# WAB_1x4_HSMC_slots.net
KiCad netlist of a schematic drawn in Altium Designer
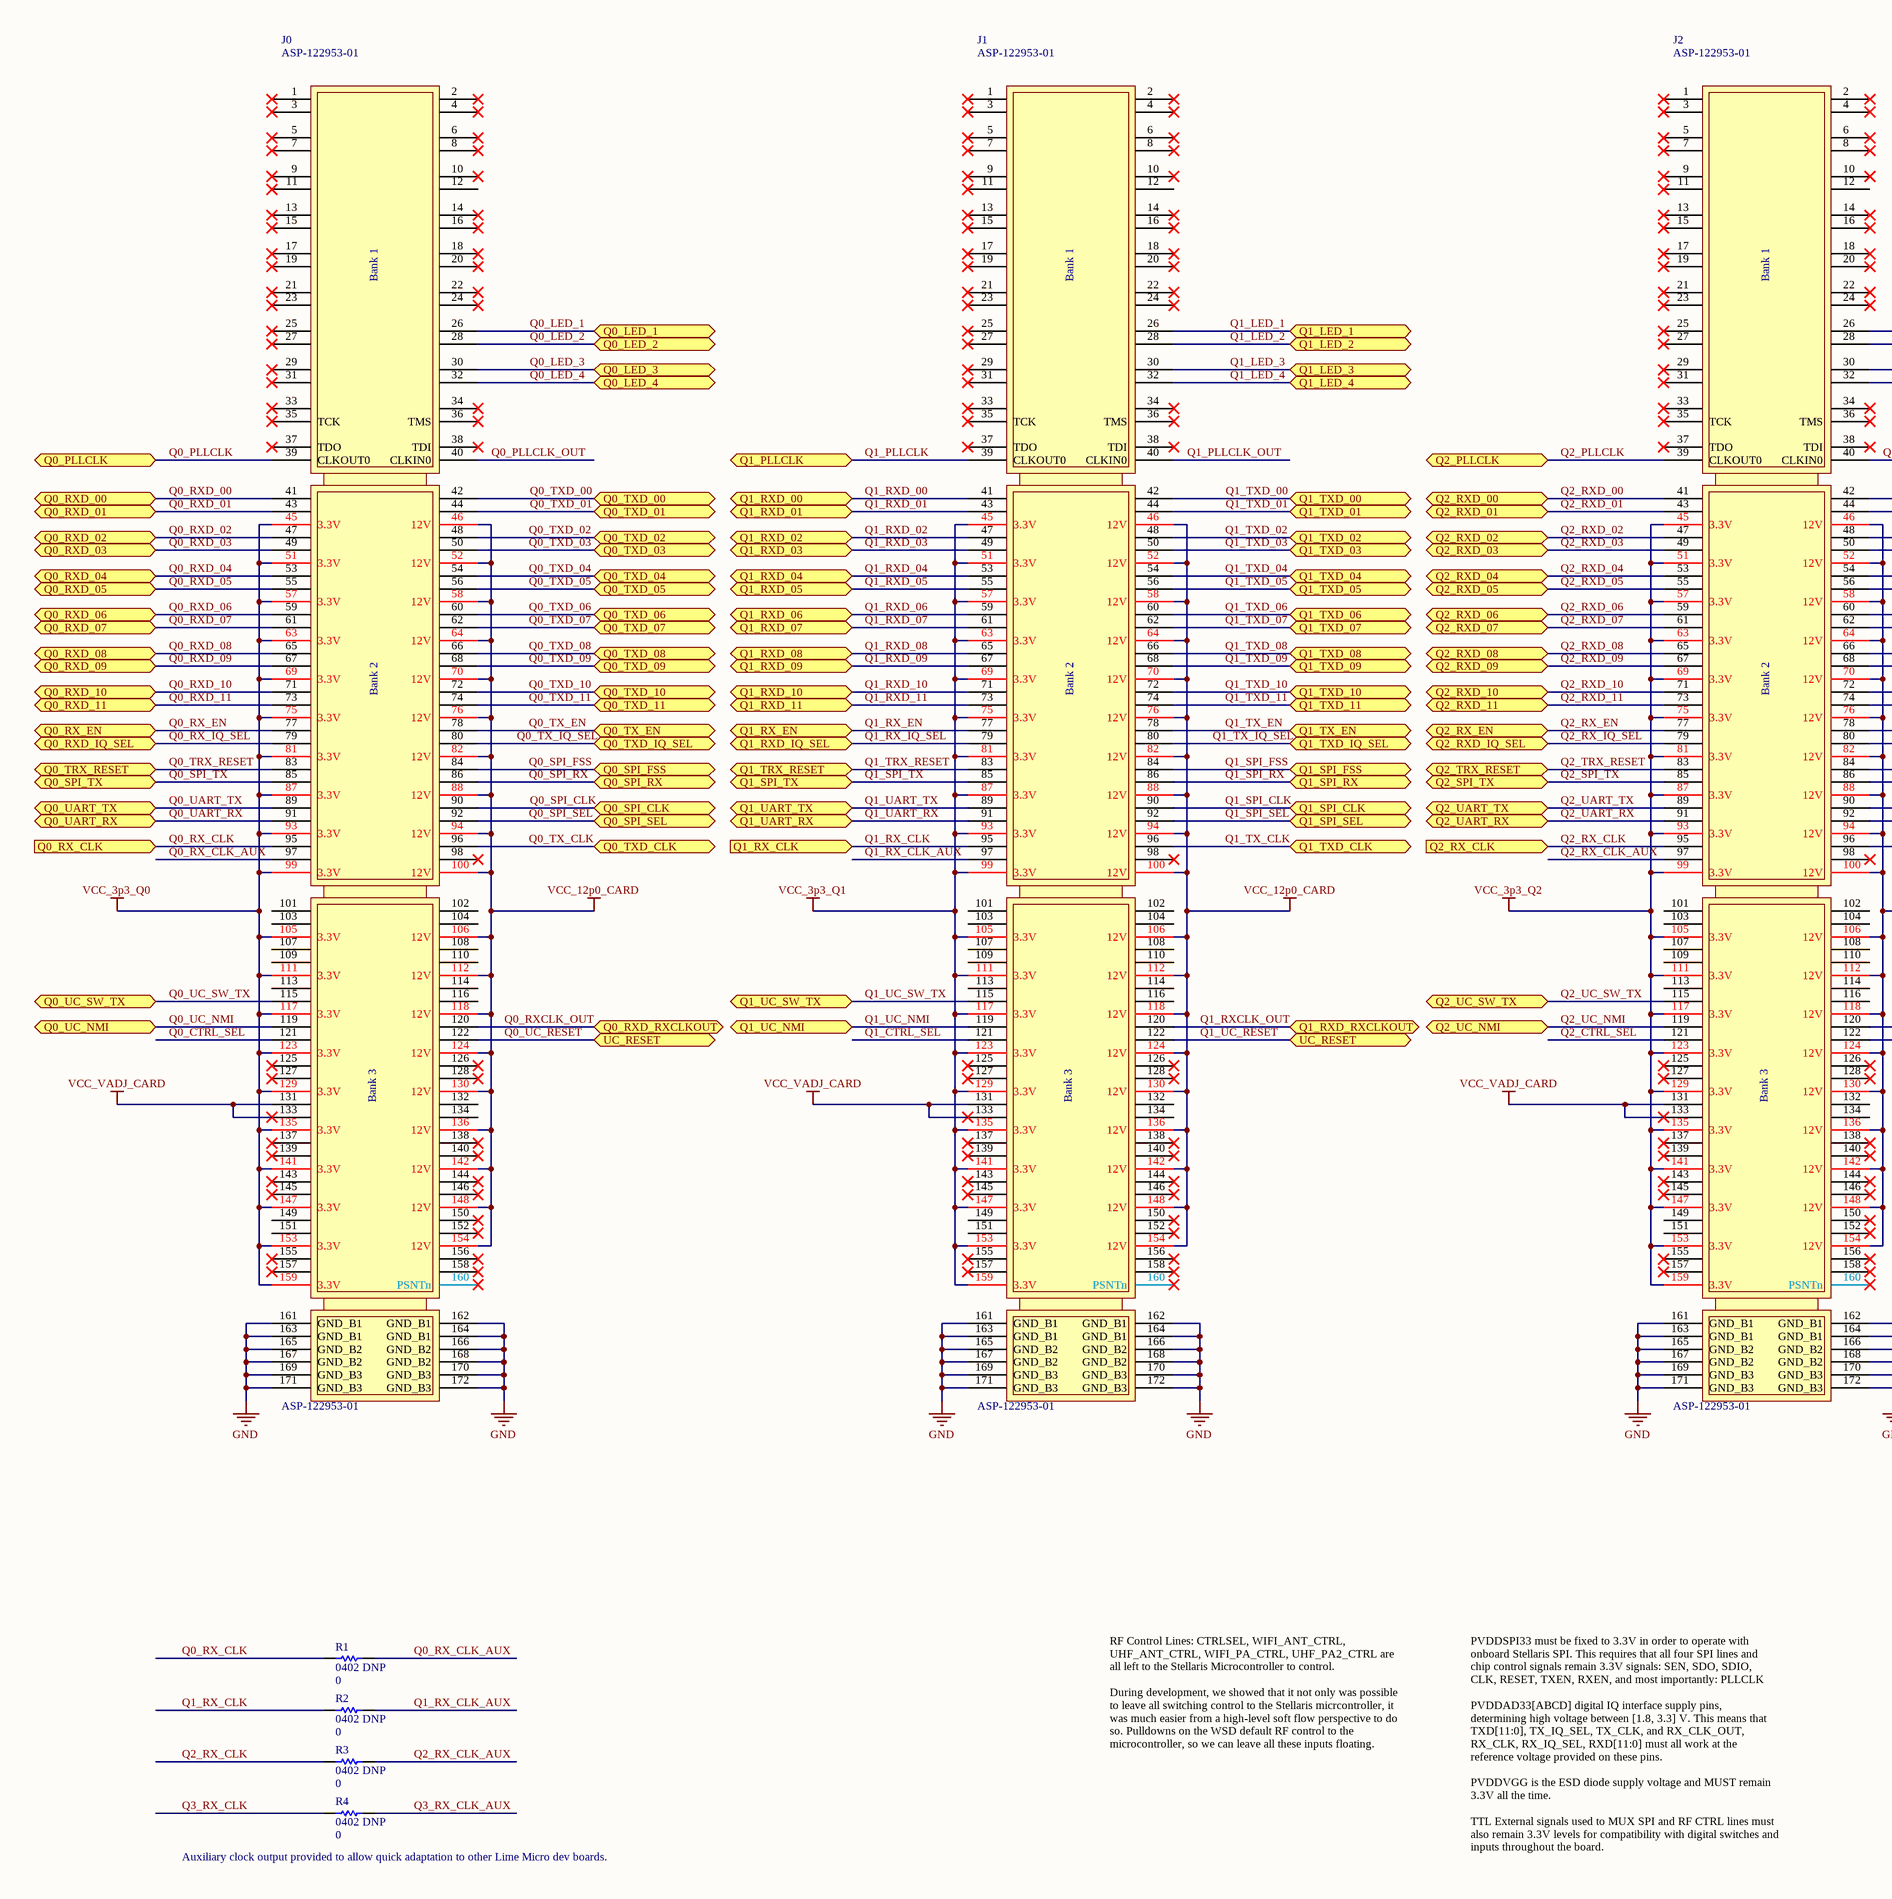
[diagram p0: WAB_1x4_HSMC_slots.SchDoc, left]
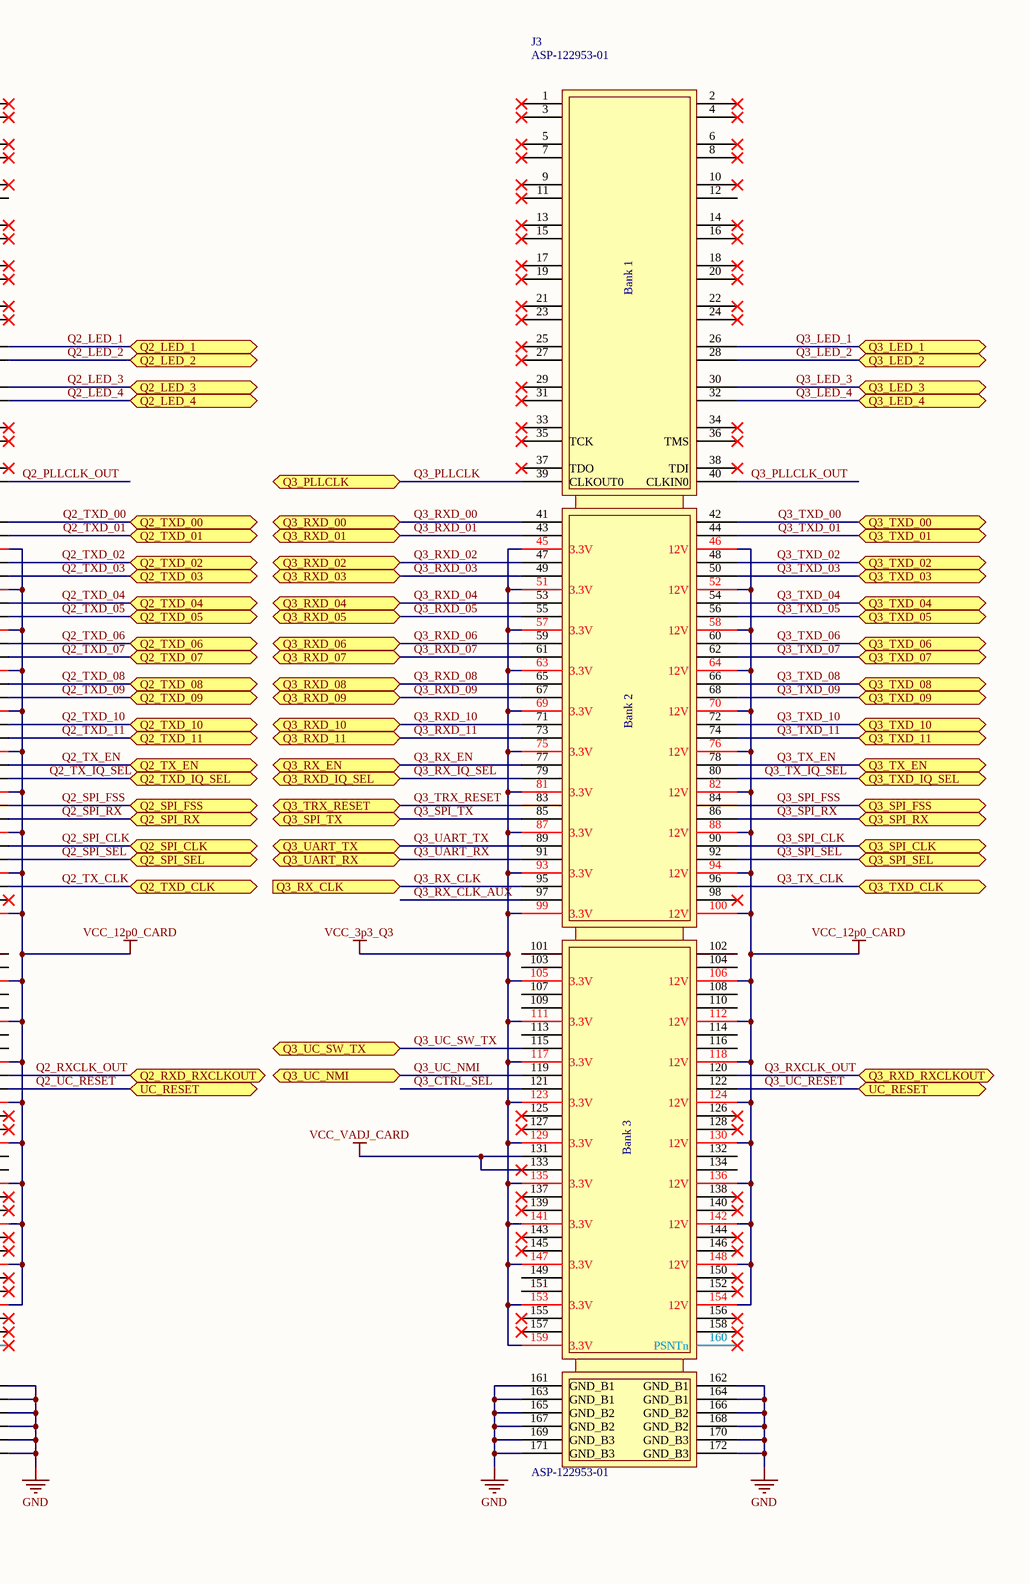
[diagram p1: WAB_1x4_HSMC_slots.SchDoc, right]

(export (version "E")
  (design (tool "Eeschema 10.0.6"))
  (components
    (comp (ref "J0")
      (value "ASP-122953-01")
      (footprint "ASP-122953-01_v3")
      (description "Samtec HSMC Host Connector (Female)")
      (libsource (lib "RNG_Parts") (part "ASP-122953-01"))
    )
    (comp (ref "J1")
      (value "ASP-122953-01")
      (footprint "ASP-122953-01_v3")
      (description "Samtec HSMC Host Connector (Female)")
      (libsource (lib "RNG_Parts") (part "ASP-122953-01"))
    )
    (comp (ref "J2")
      (value "ASP-122953-01")
      (footprint "ASP-122953-01_v3")
      (description "Samtec HSMC Host Connector (Female)")
      (libsource (lib "RNG_Parts") (part "ASP-122953-01"))
    )
    (comp (ref "J3")
      (value "ASP-122953-01")
      (footprint "ASP-122953-01_v3")
      (description "Samtec HSMC Host Connector (Female)")
      (libsource (lib "RNG_Parts") (part "ASP-122953-01"))
    )
    (comp (ref "R1")
      (value "0402 DNP")
      (footprint "0402_SMT_RES")
      (description "0402 SMT Resistor")
      (fields (field (name "ALTIUM_VALUE") "0"))
      (libsource (lib "RNG_Parts") (part "Res_0402"))
    )
    (comp (ref "R2")
      (value "0402 DNP")
      (footprint "0402_SMT_RES")
      (description "0402 SMT Resistor")
      (fields (field (name "ALTIUM_VALUE") "0"))
      (libsource (lib "RNG_Parts") (part "Res_0402"))
    )
    (comp (ref "R3")
      (value "0402 DNP")
      (footprint "0402_SMT_RES")
      (description "0402 SMT Resistor")
      (fields (field (name "ALTIUM_VALUE") "0"))
      (libsource (lib "RNG_Parts") (part "Res_0402"))
    )
    (comp (ref "R4")
      (value "0402 DNP")
      (footprint "0402_SMT_RES")
      (description "0402 SMT Resistor")
      (fields (field (name "ALTIUM_VALUE") "0"))
      (libsource (lib "RNG_Parts") (part "Res_0402"))
    )
  )
  (nets
    (net (code "1") (name "/Q0_CTRL_SEL") (class "Default")
      (node (ref "J0") (pin "121") (pinfunction "121_121") (pintype "passive"))
    )
    (net (code "2") (name "/Q0_LED_1") (class "Default")
      (node (ref "J0") (pin "26") (pinfunction "26_26") (pintype "passive"))
    )
    (net (code "3") (name "/Q0_LED_2") (class "Default")
      (node (ref "J0") (pin "28") (pinfunction "28_28") (pintype "passive"))
    )
    (net (code "4") (name "/Q0_LED_3") (class "Default")
      (node (ref "J0") (pin "30") (pinfunction "30_30") (pintype "passive"))
    )
    (net (code "5") (name "/Q0_LED_4") (class "Default")
      (node (ref "J0") (pin "32") (pinfunction "32_32") (pintype "passive"))
    )
    (net (code "6") (name "/Q0_PLLCLK") (class "Default")
      (node (ref "J0") (pin "39") (pinfunction "CLKOUT0_39") (pintype "passive"))
    )
    (net (code "7") (name "/Q0_PLLCLK_OUT") (class "Default")
      (node (ref "J0") (pin "40") (pinfunction "CLKIN0_40") (pintype "power_in"))
    )
    (net (code "8") (name "/Q0_RXCLK_OUT") (class "Default")
      (node (ref "J0") (pin "120") (pinfunction "120_120") (pintype "passive"))
    )
    (net (code "9") (name "/Q0_RXD_00") (class "Default")
      (node (ref "J0") (pin "41") (pinfunction "41_41") (pintype "passive"))
    )
    (net (code "10") (name "/Q0_RXD_01") (class "Default")
      (node (ref "J0") (pin "43") (pinfunction "43_43") (pintype "passive"))
    )
    (net (code "11") (name "/Q0_RXD_02") (class "Default")
      (node (ref "J0") (pin "47") (pinfunction "47_47") (pintype "passive"))
    )
    (net (code "12") (name "/Q0_RXD_03") (class "Default")
      (node (ref "J0") (pin "49") (pinfunction "49_49") (pintype "passive"))
    )
    (net (code "13") (name "/Q0_RXD_04") (class "Default")
      (node (ref "J0") (pin "53") (pinfunction "53_53") (pintype "passive"))
    )
    (net (code "14") (name "/Q0_RXD_05") (class "Default")
      (node (ref "J0") (pin "55") (pinfunction "55_55") (pintype "passive"))
    )
    (net (code "15") (name "/Q0_RXD_06") (class "Default")
      (node (ref "J0") (pin "59") (pinfunction "59_59") (pintype "passive"))
    )
    (net (code "16") (name "/Q0_RXD_07") (class "Default")
      (node (ref "J0") (pin "61") (pinfunction "61_61") (pintype "passive"))
    )
    (net (code "17") (name "/Q0_RXD_08") (class "Default")
      (node (ref "J0") (pin "65") (pinfunction "65_65") (pintype "passive"))
    )
    (net (code "18") (name "/Q0_RXD_09") (class "Default")
      (node (ref "J0") (pin "67") (pinfunction "67_67") (pintype "passive"))
    )
    (net (code "19") (name "/Q0_RXD_10") (class "Default")
      (node (ref "J0") (pin "71") (pinfunction "71_71") (pintype "passive"))
    )
    (net (code "20") (name "/Q0_RXD_11") (class "Default")
      (node (ref "J0") (pin "73") (pinfunction "73_73") (pintype "passive"))
    )
    (net (code "21") (name "/Q0_RX_CLK") (class "Default")
      (node (ref "J0") (pin "95") (pinfunction "95_95") (pintype "passive"))
      (node (ref "R1") (pin "1") (pinfunction "1_1") (pintype "passive"))
    )
    (net (code "22") (name "/Q0_RX_CLK_AUX") (class "Default")
      (node (ref "J0") (pin "97") (pinfunction "97_97") (pintype "passive"))
      (node (ref "R1") (pin "2") (pinfunction "2_2") (pintype "passive"))
    )
    (net (code "23") (name "/Q0_RX_EN") (class "Default")
      (node (ref "J0") (pin "77") (pinfunction "77_77") (pintype "passive"))
    )
    (net (code "24") (name "/Q0_RX_IQ_SEL") (class "Default")
      (node (ref "J0") (pin "79") (pinfunction "79_79") (pintype "passive"))
    )
    (net (code "25") (name "/Q0_SPI_CLK") (class "Default")
      (node (ref "J0") (pin "90") (pinfunction "90_90") (pintype "passive"))
    )
    (net (code "26") (name "/Q0_SPI_FSS") (class "Default")
      (node (ref "J0") (pin "84") (pinfunction "84_84") (pintype "passive"))
    )
    (net (code "27") (name "/Q0_SPI_RX") (class "Default")
      (node (ref "J0") (pin "86") (pinfunction "86_86") (pintype "passive"))
    )
    (net (code "28") (name "/Q0_SPI_SEL") (class "Default")
      (node (ref "J0") (pin "92") (pinfunction "92_92") (pintype "passive"))
    )
    (net (code "29") (name "/Q0_SPI_TX") (class "Default")
      (node (ref "J0") (pin "85") (pinfunction "85_85") (pintype "passive"))
    )
    (net (code "30") (name "/Q0_TRX_RESET") (class "Default")
      (node (ref "J0") (pin "83") (pinfunction "83_83") (pintype "passive"))
    )
    (net (code "31") (name "/Q0_TXD_00") (class "Default")
      (node (ref "J0") (pin "42") (pinfunction "42_42") (pintype "passive"))
    )
    (net (code "32") (name "/Q0_TXD_01") (class "Default")
      (node (ref "J0") (pin "44") (pinfunction "44_44") (pintype "passive"))
    )
    (net (code "33") (name "/Q0_TXD_02") (class "Default")
      (node (ref "J0") (pin "48") (pinfunction "48_48") (pintype "passive"))
    )
    (net (code "34") (name "/Q0_TXD_03") (class "Default")
      (node (ref "J0") (pin "50") (pinfunction "50_50") (pintype "passive"))
    )
    (net (code "35") (name "/Q0_TXD_04") (class "Default")
      (node (ref "J0") (pin "54") (pinfunction "54_54") (pintype "passive"))
    )
    (net (code "36") (name "/Q0_TXD_05") (class "Default")
      (node (ref "J0") (pin "56") (pinfunction "56_56") (pintype "passive"))
    )
    (net (code "37") (name "/Q0_TXD_06") (class "Default")
      (node (ref "J0") (pin "60") (pinfunction "60_60") (pintype "passive"))
    )
    (net (code "38") (name "/Q0_TXD_07") (class "Default")
      (node (ref "J0") (pin "62") (pinfunction "62_62") (pintype "passive"))
    )
    (net (code "39") (name "/Q0_TXD_08") (class "Default")
      (node (ref "J0") (pin "66") (pinfunction "66_66") (pintype "passive"))
    )
    (net (code "40") (name "/Q0_TXD_09") (class "Default")
      (node (ref "J0") (pin "68") (pinfunction "68_68") (pintype "passive"))
    )
    (net (code "41") (name "/Q0_TXD_10") (class "Default")
      (node (ref "J0") (pin "72") (pinfunction "72_72") (pintype "passive"))
    )
    (net (code "42") (name "/Q0_TXD_11") (class "Default")
      (node (ref "J0") (pin "74") (pinfunction "74_74") (pintype "passive"))
    )
    (net (code "43") (name "/Q0_TX_CLK") (class "Default")
      (node (ref "J0") (pin "96") (pinfunction "96_96") (pintype "passive"))
    )
    (net (code "44") (name "/Q0_TX_EN") (class "Default")
      (node (ref "J0") (pin "78") (pinfunction "78_78") (pintype "passive"))
    )
    (net (code "45") (name "/Q0_TX_IQ_SEL") (class "Default")
      (node (ref "J0") (pin "80") (pinfunction "80_80") (pintype "passive"))
    )
    (net (code "46") (name "/Q0_UART_RX") (class "Default")
      (node (ref "J0") (pin "91") (pinfunction "91_91") (pintype "passive"))
    )
    (net (code "47") (name "/Q0_UART_TX") (class "Default")
      (node (ref "J0") (pin "89") (pinfunction "89_89") (pintype "passive"))
    )
    (net (code "48") (name "/Q0_UC_NMI") (class "Default")
      (node (ref "J0") (pin "119") (pinfunction "119_119") (pintype "passive"))
    )
    (net (code "49") (name "/Q0_UC_RESET") (class "Default")
      (node (ref "J0") (pin "122") (pinfunction "122_122") (pintype "passive"))
      (node (ref "J1") (pin "122") (pinfunction "122_122") (pintype "passive"))
      (node (ref "J2") (pin "122") (pinfunction "122_122") (pintype "passive"))
      (node (ref "J3") (pin "122") (pinfunction "122_122") (pintype "passive"))
    )
    (net (code "50") (name "/Q0_UC_SW_TX") (class "Default")
      (node (ref "J0") (pin "115") (pinfunction "115_115") (pintype "passive"))
    )
    (net (code "51") (name "/Q1_CTRL_SEL") (class "Default")
      (node (ref "J1") (pin "121") (pinfunction "121_121") (pintype "passive"))
    )
    (net (code "52") (name "/Q1_LED_1") (class "Default")
      (node (ref "J1") (pin "26") (pinfunction "26_26") (pintype "passive"))
    )
    (net (code "53") (name "/Q1_LED_2") (class "Default")
      (node (ref "J1") (pin "28") (pinfunction "28_28") (pintype "passive"))
    )
    (net (code "54") (name "/Q1_LED_3") (class "Default")
      (node (ref "J1") (pin "30") (pinfunction "30_30") (pintype "passive"))
    )
    (net (code "55") (name "/Q1_LED_4") (class "Default")
      (node (ref "J1") (pin "32") (pinfunction "32_32") (pintype "passive"))
    )
    (net (code "56") (name "/Q1_PLLCLK") (class "Default")
      (node (ref "J1") (pin "39") (pinfunction "CLKOUT0_39") (pintype "passive"))
    )
    (net (code "57") (name "/Q1_PLLCLK_OUT") (class "Default")
      (node (ref "J1") (pin "40") (pinfunction "CLKIN0_40") (pintype "power_in"))
    )
    (net (code "58") (name "/Q1_RXCLK_OUT") (class "Default")
      (node (ref "J1") (pin "120") (pinfunction "120_120") (pintype "passive"))
    )
    (net (code "59") (name "/Q1_RXD_00") (class "Default")
      (node (ref "J1") (pin "41") (pinfunction "41_41") (pintype "passive"))
    )
    (net (code "60") (name "/Q1_RXD_01") (class "Default")
      (node (ref "J1") (pin "43") (pinfunction "43_43") (pintype "passive"))
    )
    (net (code "61") (name "/Q1_RXD_02") (class "Default")
      (node (ref "J1") (pin "47") (pinfunction "47_47") (pintype "passive"))
    )
    (net (code "62") (name "/Q1_RXD_03") (class "Default")
      (node (ref "J1") (pin "49") (pinfunction "49_49") (pintype "passive"))
    )
    (net (code "63") (name "/Q1_RXD_04") (class "Default")
      (node (ref "J1") (pin "53") (pinfunction "53_53") (pintype "passive"))
    )
    (net (code "64") (name "/Q1_RXD_05") (class "Default")
      (node (ref "J1") (pin "55") (pinfunction "55_55") (pintype "passive"))
    )
    (net (code "65") (name "/Q1_RXD_06") (class "Default")
      (node (ref "J1") (pin "59") (pinfunction "59_59") (pintype "passive"))
    )
    (net (code "66") (name "/Q1_RXD_07") (class "Default")
      (node (ref "J1") (pin "61") (pinfunction "61_61") (pintype "passive"))
    )
    (net (code "67") (name "/Q1_RXD_08") (class "Default")
      (node (ref "J1") (pin "65") (pinfunction "65_65") (pintype "passive"))
    )
    (net (code "68") (name "/Q1_RXD_09") (class "Default")
      (node (ref "J1") (pin "67") (pinfunction "67_67") (pintype "passive"))
    )
    (net (code "69") (name "/Q1_RXD_10") (class "Default")
      (node (ref "J1") (pin "71") (pinfunction "71_71") (pintype "passive"))
    )
    (net (code "70") (name "/Q1_RXD_11") (class "Default")
      (node (ref "J1") (pin "73") (pinfunction "73_73") (pintype "passive"))
    )
    (net (code "71") (name "/Q1_RX_CLK") (class "Default")
      (node (ref "J1") (pin "95") (pinfunction "95_95") (pintype "passive"))
      (node (ref "R2") (pin "1") (pinfunction "1_1") (pintype "passive"))
    )
    (net (code "72") (name "/Q1_RX_CLK_AUX") (class "Default")
      (node (ref "J1") (pin "97") (pinfunction "97_97") (pintype "passive"))
      (node (ref "R2") (pin "2") (pinfunction "2_2") (pintype "passive"))
    )
    (net (code "73") (name "/Q1_RX_EN") (class "Default")
      (node (ref "J1") (pin "77") (pinfunction "77_77") (pintype "passive"))
    )
    (net (code "74") (name "/Q1_RX_IQ_SEL") (class "Default")
      (node (ref "J1") (pin "79") (pinfunction "79_79") (pintype "passive"))
    )
    (net (code "75") (name "/Q1_SPI_CLK") (class "Default")
      (node (ref "J1") (pin "90") (pinfunction "90_90") (pintype "passive"))
    )
    (net (code "76") (name "/Q1_SPI_FSS") (class "Default")
      (node (ref "J1") (pin "84") (pinfunction "84_84") (pintype "passive"))
    )
    (net (code "77") (name "/Q1_SPI_RX") (class "Default")
      (node (ref "J1") (pin "86") (pinfunction "86_86") (pintype "passive"))
    )
    (net (code "78") (name "/Q1_SPI_SEL") (class "Default")
      (node (ref "J1") (pin "92") (pinfunction "92_92") (pintype "passive"))
    )
    (net (code "79") (name "/Q1_SPI_TX") (class "Default")
      (node (ref "J1") (pin "85") (pinfunction "85_85") (pintype "passive"))
    )
    (net (code "80") (name "/Q1_TRX_RESET") (class "Default")
      (node (ref "J1") (pin "83") (pinfunction "83_83") (pintype "passive"))
    )
    (net (code "81") (name "/Q1_TXD_00") (class "Default")
      (node (ref "J1") (pin "42") (pinfunction "42_42") (pintype "passive"))
    )
    (net (code "82") (name "/Q1_TXD_01") (class "Default")
      (node (ref "J1") (pin "44") (pinfunction "44_44") (pintype "passive"))
    )
    (net (code "83") (name "/Q1_TXD_02") (class "Default")
      (node (ref "J1") (pin "48") (pinfunction "48_48") (pintype "passive"))
    )
    (net (code "84") (name "/Q1_TXD_03") (class "Default")
      (node (ref "J1") (pin "50") (pinfunction "50_50") (pintype "passive"))
    )
    (net (code "85") (name "/Q1_TXD_04") (class "Default")
      (node (ref "J1") (pin "54") (pinfunction "54_54") (pintype "passive"))
    )
    (net (code "86") (name "/Q1_TXD_05") (class "Default")
      (node (ref "J1") (pin "56") (pinfunction "56_56") (pintype "passive"))
    )
    (net (code "87") (name "/Q1_TXD_06") (class "Default")
      (node (ref "J1") (pin "60") (pinfunction "60_60") (pintype "passive"))
    )
    (net (code "88") (name "/Q1_TXD_07") (class "Default")
      (node (ref "J1") (pin "62") (pinfunction "62_62") (pintype "passive"))
    )
    (net (code "89") (name "/Q1_TXD_08") (class "Default")
      (node (ref "J1") (pin "66") (pinfunction "66_66") (pintype "passive"))
    )
    (net (code "90") (name "/Q1_TXD_09") (class "Default")
      (node (ref "J1") (pin "68") (pinfunction "68_68") (pintype "passive"))
    )
    (net (code "91") (name "/Q1_TXD_10") (class "Default")
      (node (ref "J1") (pin "72") (pinfunction "72_72") (pintype "passive"))
    )
    (net (code "92") (name "/Q1_TXD_11") (class "Default")
      (node (ref "J1") (pin "74") (pinfunction "74_74") (pintype "passive"))
    )
    (net (code "93") (name "/Q1_TX_CLK") (class "Default")
      (node (ref "J1") (pin "96") (pinfunction "96_96") (pintype "passive"))
    )
    (net (code "94") (name "/Q1_TX_EN") (class "Default")
      (node (ref "J1") (pin "78") (pinfunction "78_78") (pintype "passive"))
    )
    (net (code "95") (name "/Q1_TX_IQ_SEL") (class "Default")
      (node (ref "J1") (pin "80") (pinfunction "80_80") (pintype "passive"))
    )
    (net (code "96") (name "/Q1_UART_RX") (class "Default")
      (node (ref "J1") (pin "91") (pinfunction "91_91") (pintype "passive"))
    )
    (net (code "97") (name "/Q1_UART_TX") (class "Default")
      (node (ref "J1") (pin "89") (pinfunction "89_89") (pintype "passive"))
    )
    (net (code "98") (name "/Q1_UC_NMI") (class "Default")
      (node (ref "J1") (pin "119") (pinfunction "119_119") (pintype "passive"))
    )
    (net (code "99") (name "/Q1_UC_SW_TX") (class "Default")
      (node (ref "J1") (pin "115") (pinfunction "115_115") (pintype "passive"))
    )
    (net (code "100") (name "/Q2_CTRL_SEL") (class "Default")
      (node (ref "J2") (pin "121") (pinfunction "121_121") (pintype "passive"))
    )
    (net (code "101") (name "/Q2_LED_1") (class "Default")
      (node (ref "J2") (pin "26") (pinfunction "26_26") (pintype "passive"))
    )
    (net (code "102") (name "/Q2_LED_2") (class "Default")
      (node (ref "J2") (pin "28") (pinfunction "28_28") (pintype "passive"))
    )
    (net (code "103") (name "/Q2_LED_3") (class "Default")
      (node (ref "J2") (pin "30") (pinfunction "30_30") (pintype "passive"))
    )
    (net (code "104") (name "/Q2_LED_4") (class "Default")
      (node (ref "J2") (pin "32") (pinfunction "32_32") (pintype "passive"))
    )
    (net (code "105") (name "/Q2_PLLCLK") (class "Default")
      (node (ref "J2") (pin "39") (pinfunction "CLKOUT0_39") (pintype "passive"))
    )
    (net (code "106") (name "/Q2_PLLCLK_OUT") (class "Default")
      (node (ref "J2") (pin "40") (pinfunction "CLKIN0_40") (pintype "power_in"))
    )
    (net (code "107") (name "/Q2_RXCLK_OUT") (class "Default")
      (node (ref "J2") (pin "120") (pinfunction "120_120") (pintype "passive"))
    )
    (net (code "108") (name "/Q2_RXD_00") (class "Default")
      (node (ref "J2") (pin "41") (pinfunction "41_41") (pintype "passive"))
    )
    (net (code "109") (name "/Q2_RXD_01") (class "Default")
      (node (ref "J2") (pin "43") (pinfunction "43_43") (pintype "passive"))
    )
    (net (code "110") (name "/Q2_RXD_02") (class "Default")
      (node (ref "J2") (pin "47") (pinfunction "47_47") (pintype "passive"))
    )
    (net (code "111") (name "/Q2_RXD_03") (class "Default")
      (node (ref "J2") (pin "49") (pinfunction "49_49") (pintype "passive"))
    )
    (net (code "112") (name "/Q2_RXD_04") (class "Default")
      (node (ref "J2") (pin "53") (pinfunction "53_53") (pintype "passive"))
    )
    (net (code "113") (name "/Q2_RXD_05") (class "Default")
      (node (ref "J2") (pin "55") (pinfunction "55_55") (pintype "passive"))
    )
    (net (code "114") (name "/Q2_RXD_06") (class "Default")
      (node (ref "J2") (pin "59") (pinfunction "59_59") (pintype "passive"))
    )
    (net (code "115") (name "/Q2_RXD_07") (class "Default")
      (node (ref "J2") (pin "61") (pinfunction "61_61") (pintype "passive"))
    )
    (net (code "116") (name "/Q2_RXD_08") (class "Default")
      (node (ref "J2") (pin "65") (pinfunction "65_65") (pintype "passive"))
    )
    (net (code "117") (name "/Q2_RXD_09") (class "Default")
      (node (ref "J2") (pin "67") (pinfunction "67_67") (pintype "passive"))
    )
    (net (code "118") (name "/Q2_RXD_10") (class "Default")
      (node (ref "J2") (pin "71") (pinfunction "71_71") (pintype "passive"))
    )
    (net (code "119") (name "/Q2_RXD_11") (class "Default")
      (node (ref "J2") (pin "73") (pinfunction "73_73") (pintype "passive"))
    )
    (net (code "120") (name "/Q2_RX_CLK") (class "Default")
      (node (ref "J2") (pin "95") (pinfunction "95_95") (pintype "passive"))
      (node (ref "R3") (pin "1") (pinfunction "1_1") (pintype "passive"))
    )
    (net (code "121") (name "/Q2_RX_CLK_AUX") (class "Default")
      (node (ref "J2") (pin "97") (pinfunction "97_97") (pintype "passive"))
      (node (ref "R3") (pin "2") (pinfunction "2_2") (pintype "passive"))
    )
    (net (code "122") (name "/Q2_RX_EN") (class "Default")
      (node (ref "J2") (pin "77") (pinfunction "77_77") (pintype "passive"))
    )
    (net (code "123") (name "/Q2_RX_IQ_SEL") (class "Default")
      (node (ref "J2") (pin "79") (pinfunction "79_79") (pintype "passive"))
    )
    (net (code "124") (name "/Q2_SPI_CLK") (class "Default")
      (node (ref "J2") (pin "90") (pinfunction "90_90") (pintype "passive"))
    )
    (net (code "125") (name "/Q2_SPI_FSS") (class "Default")
      (node (ref "J2") (pin "84") (pinfunction "84_84") (pintype "passive"))
    )
    (net (code "126") (name "/Q2_SPI_RX") (class "Default")
      (node (ref "J2") (pin "86") (pinfunction "86_86") (pintype "passive"))
    )
    (net (code "127") (name "/Q2_SPI_SEL") (class "Default")
      (node (ref "J2") (pin "92") (pinfunction "92_92") (pintype "passive"))
    )
    (net (code "128") (name "/Q2_SPI_TX") (class "Default")
      (node (ref "J2") (pin "85") (pinfunction "85_85") (pintype "passive"))
    )
    (net (code "129") (name "/Q2_TRX_RESET") (class "Default")
      (node (ref "J2") (pin "83") (pinfunction "83_83") (pintype "passive"))
    )
    (net (code "130") (name "/Q2_TXD_00") (class "Default")
      (node (ref "J2") (pin "42") (pinfunction "42_42") (pintype "passive"))
    )
    (net (code "131") (name "/Q2_TXD_01") (class "Default")
      (node (ref "J2") (pin "44") (pinfunction "44_44") (pintype "passive"))
    )
    (net (code "132") (name "/Q2_TXD_02") (class "Default")
      (node (ref "J2") (pin "48") (pinfunction "48_48") (pintype "passive"))
    )
    (net (code "133") (name "/Q2_TXD_03") (class "Default")
      (node (ref "J2") (pin "50") (pinfunction "50_50") (pintype "passive"))
    )
    (net (code "134") (name "/Q2_TXD_04") (class "Default")
      (node (ref "J2") (pin "54") (pinfunction "54_54") (pintype "passive"))
    )
    (net (code "135") (name "/Q2_TXD_05") (class "Default")
      (node (ref "J2") (pin "56") (pinfunction "56_56") (pintype "passive"))
    )
    (net (code "136") (name "/Q2_TXD_06") (class "Default")
      (node (ref "J2") (pin "60") (pinfunction "60_60") (pintype "passive"))
    )
    (net (code "137") (name "/Q2_TXD_07") (class "Default")
      (node (ref "J2") (pin "62") (pinfunction "62_62") (pintype "passive"))
    )
    (net (code "138") (name "/Q2_TXD_08") (class "Default")
      (node (ref "J2") (pin "66") (pinfunction "66_66") (pintype "passive"))
    )
    (net (code "139") (name "/Q2_TXD_09") (class "Default")
      (node (ref "J2") (pin "68") (pinfunction "68_68") (pintype "passive"))
    )
    (net (code "140") (name "/Q2_TXD_10") (class "Default")
      (node (ref "J2") (pin "72") (pinfunction "72_72") (pintype "passive"))
    )
    (net (code "141") (name "/Q2_TXD_11") (class "Default")
      (node (ref "J2") (pin "74") (pinfunction "74_74") (pintype "passive"))
    )
    (net (code "142") (name "/Q2_TX_CLK") (class "Default")
      (node (ref "J2") (pin "96") (pinfunction "96_96") (pintype "passive"))
    )
    (net (code "143") (name "/Q2_TX_EN") (class "Default")
      (node (ref "J2") (pin "78") (pinfunction "78_78") (pintype "passive"))
    )
    (net (code "144") (name "/Q2_TX_IQ_SEL") (class "Default")
      (node (ref "J2") (pin "80") (pinfunction "80_80") (pintype "passive"))
    )
    (net (code "145") (name "/Q2_UART_RX") (class "Default")
      (node (ref "J2") (pin "91") (pinfunction "91_91") (pintype "passive"))
    )
    (net (code "146") (name "/Q2_UART_TX") (class "Default")
      (node (ref "J2") (pin "89") (pinfunction "89_89") (pintype "passive"))
    )
    (net (code "147") (name "/Q2_UC_NMI") (class "Default")
      (node (ref "J2") (pin "119") (pinfunction "119_119") (pintype "passive"))
    )
    (net (code "148") (name "/Q2_UC_SW_TX") (class "Default")
      (node (ref "J2") (pin "115") (pinfunction "115_115") (pintype "passive"))
    )
    (net (code "149") (name "/Q3_CTRL_SEL") (class "Default")
      (node (ref "J3") (pin "121") (pinfunction "121_121") (pintype "passive"))
    )
    (net (code "150") (name "/Q3_LED_1") (class "Default")
      (node (ref "J3") (pin "26") (pinfunction "26_26") (pintype "passive"))
    )
    (net (code "151") (name "/Q3_LED_2") (class "Default")
      (node (ref "J3") (pin "28") (pinfunction "28_28") (pintype "passive"))
    )
    (net (code "152") (name "/Q3_LED_3") (class "Default")
      (node (ref "J3") (pin "30") (pinfunction "30_30") (pintype "passive"))
    )
    (net (code "153") (name "/Q3_LED_4") (class "Default")
      (node (ref "J3") (pin "32") (pinfunction "32_32") (pintype "passive"))
    )
    (net (code "154") (name "/Q3_PLLCLK") (class "Default")
      (node (ref "J3") (pin "39") (pinfunction "CLKOUT0_39") (pintype "passive"))
    )
    (net (code "155") (name "/Q3_PLLCLK_OUT") (class "Default")
      (node (ref "J3") (pin "40") (pinfunction "CLKIN0_40") (pintype "power_in"))
    )
    (net (code "156") (name "/Q3_RXCLK_OUT") (class "Default")
      (node (ref "J3") (pin "120") (pinfunction "120_120") (pintype "passive"))
    )
    (net (code "157") (name "/Q3_RXD_00") (class "Default")
      (node (ref "J3") (pin "41") (pinfunction "41_41") (pintype "passive"))
    )
    (net (code "158") (name "/Q3_RXD_01") (class "Default")
      (node (ref "J3") (pin "43") (pinfunction "43_43") (pintype "passive"))
    )
    (net (code "159") (name "/Q3_RXD_02") (class "Default")
      (node (ref "J3") (pin "47") (pinfunction "47_47") (pintype "passive"))
    )
    (net (code "160") (name "/Q3_RXD_03") (class "Default")
      (node (ref "J3") (pin "49") (pinfunction "49_49") (pintype "passive"))
    )
    (net (code "161") (name "/Q3_RXD_04") (class "Default")
      (node (ref "J3") (pin "53") (pinfunction "53_53") (pintype "passive"))
    )
    (net (code "162") (name "/Q3_RXD_05") (class "Default")
      (node (ref "J3") (pin "55") (pinfunction "55_55") (pintype "passive"))
    )
    (net (code "163") (name "/Q3_RXD_06") (class "Default")
      (node (ref "J3") (pin "59") (pinfunction "59_59") (pintype "passive"))
    )
    (net (code "164") (name "/Q3_RXD_07") (class "Default")
      (node (ref "J3") (pin "61") (pinfunction "61_61") (pintype "passive"))
    )
    (net (code "165") (name "/Q3_RXD_08") (class "Default")
      (node (ref "J3") (pin "65") (pinfunction "65_65") (pintype "passive"))
    )
    (net (code "166") (name "/Q3_RXD_09") (class "Default")
      (node (ref "J3") (pin "67") (pinfunction "67_67") (pintype "passive"))
    )
    (net (code "167") (name "/Q3_RXD_10") (class "Default")
      (node (ref "J3") (pin "71") (pinfunction "71_71") (pintype "passive"))
    )
    (net (code "168") (name "/Q3_RXD_11") (class "Default")
      (node (ref "J3") (pin "73") (pinfunction "73_73") (pintype "passive"))
    )
    (net (code "169") (name "/Q3_RX_CLK") (class "Default")
      (node (ref "J3") (pin "95") (pinfunction "95_95") (pintype "passive"))
      (node (ref "R4") (pin "1") (pinfunction "1_1") (pintype "passive"))
    )
    (net (code "170") (name "/Q3_RX_CLK_AUX") (class "Default")
      (node (ref "J3") (pin "97") (pinfunction "97_97") (pintype "passive"))
      (node (ref "R4") (pin "2") (pinfunction "2_2") (pintype "passive"))
    )
    (net (code "171") (name "/Q3_RX_EN") (class "Default")
      (node (ref "J3") (pin "77") (pinfunction "77_77") (pintype "passive"))
    )
    (net (code "172") (name "/Q3_RX_IQ_SEL") (class "Default")
      (node (ref "J3") (pin "79") (pinfunction "79_79") (pintype "passive"))
    )
    (net (code "173") (name "/Q3_SPI_CLK") (class "Default")
      (node (ref "J3") (pin "90") (pinfunction "90_90") (pintype "passive"))
    )
    (net (code "174") (name "/Q3_SPI_FSS") (class "Default")
      (node (ref "J3") (pin "84") (pinfunction "84_84") (pintype "passive"))
    )
    (net (code "175") (name "/Q3_SPI_RX") (class "Default")
      (node (ref "J3") (pin "86") (pinfunction "86_86") (pintype "passive"))
    )
    (net (code "176") (name "/Q3_SPI_SEL") (class "Default")
      (node (ref "J3") (pin "92") (pinfunction "92_92") (pintype "passive"))
    )
    (net (code "177") (name "/Q3_SPI_TX") (class "Default")
      (node (ref "J3") (pin "85") (pinfunction "85_85") (pintype "passive"))
    )
    (net (code "178") (name "/Q3_TRX_RESET") (class "Default")
      (node (ref "J3") (pin "83") (pinfunction "83_83") (pintype "passive"))
    )
    (net (code "179") (name "/Q3_TXD_00") (class "Default")
      (node (ref "J3") (pin "42") (pinfunction "42_42") (pintype "passive"))
    )
    (net (code "180") (name "/Q3_TXD_01") (class "Default")
      (node (ref "J3") (pin "44") (pinfunction "44_44") (pintype "passive"))
    )
    (net (code "181") (name "/Q3_TXD_02") (class "Default")
      (node (ref "J3") (pin "48") (pinfunction "48_48") (pintype "passive"))
    )
    (net (code "182") (name "/Q3_TXD_03") (class "Default")
      (node (ref "J3") (pin "50") (pinfunction "50_50") (pintype "passive"))
    )
    (net (code "183") (name "/Q3_TXD_04") (class "Default")
      (node (ref "J3") (pin "54") (pinfunction "54_54") (pintype "passive"))
    )
    (net (code "184") (name "/Q3_TXD_05") (class "Default")
      (node (ref "J3") (pin "56") (pinfunction "56_56") (pintype "passive"))
    )
    (net (code "185") (name "/Q3_TXD_06") (class "Default")
      (node (ref "J3") (pin "60") (pinfunction "60_60") (pintype "passive"))
    )
    (net (code "186") (name "/Q3_TXD_07") (class "Default")
      (node (ref "J3") (pin "62") (pinfunction "62_62") (pintype "passive"))
    )
    (net (code "187") (name "/Q3_TXD_08") (class "Default")
      (node (ref "J3") (pin "66") (pinfunction "66_66") (pintype "passive"))
    )
    (net (code "188") (name "/Q3_TXD_09") (class "Default")
      (node (ref "J3") (pin "68") (pinfunction "68_68") (pintype "passive"))
    )
    (net (code "189") (name "/Q3_TXD_10") (class "Default")
      (node (ref "J3") (pin "72") (pinfunction "72_72") (pintype "passive"))
    )
    (net (code "190") (name "/Q3_TXD_11") (class "Default")
      (node (ref "J3") (pin "74") (pinfunction "74_74") (pintype "passive"))
    )
    (net (code "191") (name "/Q3_TX_CLK") (class "Default")
      (node (ref "J3") (pin "96") (pinfunction "96_96") (pintype "passive"))
    )
    (net (code "192") (name "/Q3_TX_EN") (class "Default")
      (node (ref "J3") (pin "78") (pinfunction "78_78") (pintype "passive"))
    )
    (net (code "193") (name "/Q3_TX_IQ_SEL") (class "Default")
      (node (ref "J3") (pin "80") (pinfunction "80_80") (pintype "passive"))
    )
    (net (code "194") (name "/Q3_UART_RX") (class "Default")
      (node (ref "J3") (pin "91") (pinfunction "91_91") (pintype "passive"))
    )
    (net (code "195") (name "/Q3_UART_TX") (class "Default")
      (node (ref "J3") (pin "89") (pinfunction "89_89") (pintype "passive"))
    )
    (net (code "196") (name "/Q3_UC_NMI") (class "Default")
      (node (ref "J3") (pin "119") (pinfunction "119_119") (pintype "passive"))
    )
    (net (code "197") (name "/Q3_UC_SW_TX") (class "Default")
      (node (ref "J3") (pin "115") (pinfunction "115_115") (pintype "passive"))
    )
    (net (code "198") (name "GND") (class "Default")
      (node (ref "J0") (pin "161") (pinfunction "GND_B1_161") (pintype "power_in"))
      (node (ref "J0") (pin "162") (pinfunction "GND_B1_162") (pintype "power_in"))
      (node (ref "J0") (pin "163") (pinfunction "GND_B1_163") (pintype "power_in"))
      (node (ref "J0") (pin "164") (pinfunction "GND_B1_164") (pintype "power_in"))
      (node (ref "J0") (pin "165") (pinfunction "GND_B2_165") (pintype "power_in"))
      (node (ref "J0") (pin "166") (pinfunction "GND_B2_166") (pintype "power_in"))
      (node (ref "J0") (pin "167") (pinfunction "GND_B2_167") (pintype "power_in"))
      (node (ref "J0") (pin "168") (pinfunction "GND_B2_168") (pintype "power_in"))
      (node (ref "J0") (pin "169") (pinfunction "GND_B3_169") (pintype "power_in"))
      (node (ref "J0") (pin "170") (pinfunction "GND_B3_170") (pintype "power_in"))
      (node (ref "J0") (pin "171") (pinfunction "GND_B3_171") (pintype "power_in"))
      (node (ref "J0") (pin "172") (pinfunction "GND_B3_172") (pintype "power_in"))
      (node (ref "J1") (pin "161") (pinfunction "GND_B1_161") (pintype "power_in"))
      (node (ref "J1") (pin "162") (pinfunction "GND_B1_162") (pintype "power_in"))
      (node (ref "J1") (pin "163") (pinfunction "GND_B1_163") (pintype "power_in"))
      (node (ref "J1") (pin "164") (pinfunction "GND_B1_164") (pintype "power_in"))
      (node (ref "J1") (pin "165") (pinfunction "GND_B2_165") (pintype "power_in"))
      (node (ref "J1") (pin "166") (pinfunction "GND_B2_166") (pintype "power_in"))
      (node (ref "J1") (pin "167") (pinfunction "GND_B2_167") (pintype "power_in"))
      (node (ref "J1") (pin "168") (pinfunction "GND_B2_168") (pintype "power_in"))
      (node (ref "J1") (pin "169") (pinfunction "GND_B3_169") (pintype "power_in"))
      (node (ref "J1") (pin "170") (pinfunction "GND_B3_170") (pintype "power_in"))
      (node (ref "J1") (pin "171") (pinfunction "GND_B3_171") (pintype "power_in"))
      (node (ref "J1") (pin "172") (pinfunction "GND_B3_172") (pintype "power_in"))
      (node (ref "J2") (pin "161") (pinfunction "GND_B1_161") (pintype "power_in"))
      (node (ref "J2") (pin "162") (pinfunction "GND_B1_162") (pintype "power_in"))
      (node (ref "J2") (pin "163") (pinfunction "GND_B1_163") (pintype "power_in"))
      (node (ref "J2") (pin "164") (pinfunction "GND_B1_164") (pintype "power_in"))
      (node (ref "J2") (pin "165") (pinfunction "GND_B2_165") (pintype "power_in"))
      (node (ref "J2") (pin "166") (pinfunction "GND_B2_166") (pintype "power_in"))
      (node (ref "J2") (pin "167") (pinfunction "GND_B2_167") (pintype "power_in"))
      (node (ref "J2") (pin "168") (pinfunction "GND_B2_168") (pintype "power_in"))
      (node (ref "J2") (pin "169") (pinfunction "GND_B3_169") (pintype "power_in"))
      (node (ref "J2") (pin "170") (pinfunction "GND_B3_170") (pintype "power_in"))
      (node (ref "J2") (pin "171") (pinfunction "GND_B3_171") (pintype "power_in"))
      (node (ref "J2") (pin "172") (pinfunction "GND_B3_172") (pintype "power_in"))
      (node (ref "J3") (pin "161") (pinfunction "GND_B1_161") (pintype "power_in"))
      (node (ref "J3") (pin "162") (pinfunction "GND_B1_162") (pintype "power_in"))
      (node (ref "J3") (pin "163") (pinfunction "GND_B1_163") (pintype "power_in"))
      (node (ref "J3") (pin "164") (pinfunction "GND_B1_164") (pintype "power_in"))
      (node (ref "J3") (pin "165") (pinfunction "GND_B2_165") (pintype "power_in"))
      (node (ref "J3") (pin "166") (pinfunction "GND_B2_166") (pintype "power_in"))
      (node (ref "J3") (pin "167") (pinfunction "GND_B2_167") (pintype "power_in"))
      (node (ref "J3") (pin "168") (pinfunction "GND_B2_168") (pintype "power_in"))
      (node (ref "J3") (pin "169") (pinfunction "GND_B3_169") (pintype "power_in"))
      (node (ref "J3") (pin "170") (pinfunction "GND_B3_170") (pintype "power_in"))
      (node (ref "J3") (pin "171") (pinfunction "GND_B3_171") (pintype "power_in"))
      (node (ref "J3") (pin "172") (pinfunction "GND_B3_172") (pintype "power_in"))
    )
    (net (code "199") (name "VCC_3p3_Q0") (class "Default")
      (node (ref "J0") (pin "105") (pinfunction "3.3V_105") (pintype "power_in"))
      (node (ref "J0") (pin "111") (pinfunction "3.3V_111") (pintype "power_in"))
      (node (ref "J0") (pin "117") (pinfunction "3.3V_117") (pintype "power_in"))
      (node (ref "J0") (pin "123") (pinfunction "3.3V_123") (pintype "power_in"))
      (node (ref "J0") (pin "129") (pinfunction "3.3V_129") (pintype "power_in"))
      (node (ref "J0") (pin "135") (pinfunction "3.3V_135") (pintype "power_in"))
      (node (ref "J0") (pin "141") (pinfunction "3.3V_141") (pintype "power_in"))
      (node (ref "J0") (pin "147") (pinfunction "3.3V_147") (pintype "power_in"))
      (node (ref "J0") (pin "153") (pinfunction "3.3V_153") (pintype "power_in"))
      (node (ref "J0") (pin "159") (pinfunction "3.3V_159") (pintype "power_in"))
      (node (ref "J0") (pin "45") (pinfunction "3.3V_45") (pintype "power_in"))
      (node (ref "J0") (pin "51") (pinfunction "3.3V_51") (pintype "power_in"))
      (node (ref "J0") (pin "57") (pinfunction "3.3V_57") (pintype "power_in"))
      (node (ref "J0") (pin "63") (pinfunction "3.3V_63") (pintype "power_in"))
      (node (ref "J0") (pin "69") (pinfunction "3.3V_69") (pintype "power_in"))
      (node (ref "J0") (pin "75") (pinfunction "3.3V_75") (pintype "power_in"))
      (node (ref "J0") (pin "81") (pinfunction "3.3V_81") (pintype "power_in"))
      (node (ref "J0") (pin "87") (pinfunction "3.3V_87") (pintype "power_in"))
      (node (ref "J0") (pin "93") (pinfunction "3.3V_93") (pintype "power_in"))
      (node (ref "J0") (pin "99") (pinfunction "3.3V_99") (pintype "power_in"))
    )
    (net (code "200") (name "VCC_3p3_Q1") (class "Default")
      (node (ref "J1") (pin "105") (pinfunction "3.3V_105") (pintype "power_in"))
      (node (ref "J1") (pin "111") (pinfunction "3.3V_111") (pintype "power_in"))
      (node (ref "J1") (pin "117") (pinfunction "3.3V_117") (pintype "power_in"))
      (node (ref "J1") (pin "123") (pinfunction "3.3V_123") (pintype "power_in"))
      (node (ref "J1") (pin "129") (pinfunction "3.3V_129") (pintype "power_in"))
      (node (ref "J1") (pin "135") (pinfunction "3.3V_135") (pintype "power_in"))
      (node (ref "J1") (pin "141") (pinfunction "3.3V_141") (pintype "power_in"))
      (node (ref "J1") (pin "147") (pinfunction "3.3V_147") (pintype "power_in"))
      (node (ref "J1") (pin "153") (pinfunction "3.3V_153") (pintype "power_in"))
      (node (ref "J1") (pin "159") (pinfunction "3.3V_159") (pintype "power_in"))
      (node (ref "J1") (pin "45") (pinfunction "3.3V_45") (pintype "power_in"))
      (node (ref "J1") (pin "51") (pinfunction "3.3V_51") (pintype "power_in"))
      (node (ref "J1") (pin "57") (pinfunction "3.3V_57") (pintype "power_in"))
      (node (ref "J1") (pin "63") (pinfunction "3.3V_63") (pintype "power_in"))
      (node (ref "J1") (pin "69") (pinfunction "3.3V_69") (pintype "power_in"))
      (node (ref "J1") (pin "75") (pinfunction "3.3V_75") (pintype "power_in"))
      (node (ref "J1") (pin "81") (pinfunction "3.3V_81") (pintype "power_in"))
      (node (ref "J1") (pin "87") (pinfunction "3.3V_87") (pintype "power_in"))
      (node (ref "J1") (pin "93") (pinfunction "3.3V_93") (pintype "power_in"))
      (node (ref "J1") (pin "99") (pinfunction "3.3V_99") (pintype "power_in"))
    )
    (net (code "201") (name "VCC_3p3_Q2") (class "Default")
      (node (ref "J2") (pin "105") (pinfunction "3.3V_105") (pintype "power_in"))
      (node (ref "J2") (pin "111") (pinfunction "3.3V_111") (pintype "power_in"))
      (node (ref "J2") (pin "117") (pinfunction "3.3V_117") (pintype "power_in"))
      (node (ref "J2") (pin "123") (pinfunction "3.3V_123") (pintype "power_in"))
      (node (ref "J2") (pin "129") (pinfunction "3.3V_129") (pintype "power_in"))
      (node (ref "J2") (pin "135") (pinfunction "3.3V_135") (pintype "power_in"))
      (node (ref "J2") (pin "141") (pinfunction "3.3V_141") (pintype "power_in"))
      (node (ref "J2") (pin "147") (pinfunction "3.3V_147") (pintype "power_in"))
      (node (ref "J2") (pin "153") (pinfunction "3.3V_153") (pintype "power_in"))
      (node (ref "J2") (pin "159") (pinfunction "3.3V_159") (pintype "power_in"))
      (node (ref "J2") (pin "45") (pinfunction "3.3V_45") (pintype "power_in"))
      (node (ref "J2") (pin "51") (pinfunction "3.3V_51") (pintype "power_in"))
      (node (ref "J2") (pin "57") (pinfunction "3.3V_57") (pintype "power_in"))
      (node (ref "J2") (pin "63") (pinfunction "3.3V_63") (pintype "power_in"))
      (node (ref "J2") (pin "69") (pinfunction "3.3V_69") (pintype "power_in"))
      (node (ref "J2") (pin "75") (pinfunction "3.3V_75") (pintype "power_in"))
      (node (ref "J2") (pin "81") (pinfunction "3.3V_81") (pintype "power_in"))
      (node (ref "J2") (pin "87") (pinfunction "3.3V_87") (pintype "power_in"))
      (node (ref "J2") (pin "93") (pinfunction "3.3V_93") (pintype "power_in"))
      (node (ref "J2") (pin "99") (pinfunction "3.3V_99") (pintype "power_in"))
    )
    (net (code "202") (name "VCC_3p3_Q3") (class "Default")
      (node (ref "J3") (pin "105") (pinfunction "3.3V_105") (pintype "power_in"))
      (node (ref "J3") (pin "111") (pinfunction "3.3V_111") (pintype "power_in"))
      (node (ref "J3") (pin "117") (pinfunction "3.3V_117") (pintype "power_in"))
      (node (ref "J3") (pin "123") (pinfunction "3.3V_123") (pintype "power_in"))
      (node (ref "J3") (pin "129") (pinfunction "3.3V_129") (pintype "power_in"))
      (node (ref "J3") (pin "135") (pinfunction "3.3V_135") (pintype "power_in"))
      (node (ref "J3") (pin "141") (pinfunction "3.3V_141") (pintype "power_in"))
      (node (ref "J3") (pin "147") (pinfunction "3.3V_147") (pintype "power_in"))
      (node (ref "J3") (pin "153") (pinfunction "3.3V_153") (pintype "power_in"))
      (node (ref "J3") (pin "159") (pinfunction "3.3V_159") (pintype "power_in"))
      (node (ref "J3") (pin "45") (pinfunction "3.3V_45") (pintype "power_in"))
      (node (ref "J3") (pin "51") (pinfunction "3.3V_51") (pintype "power_in"))
      (node (ref "J3") (pin "57") (pinfunction "3.3V_57") (pintype "power_in"))
      (node (ref "J3") (pin "63") (pinfunction "3.3V_63") (pintype "power_in"))
      (node (ref "J3") (pin "69") (pinfunction "3.3V_69") (pintype "power_in"))
      (node (ref "J3") (pin "75") (pinfunction "3.3V_75") (pintype "power_in"))
      (node (ref "J3") (pin "81") (pinfunction "3.3V_81") (pintype "power_in"))
      (node (ref "J3") (pin "87") (pinfunction "3.3V_87") (pintype "power_in"))
      (node (ref "J3") (pin "93") (pinfunction "3.3V_93") (pintype "power_in"))
      (node (ref "J3") (pin "99") (pinfunction "3.3V_99") (pintype "power_in"))
    )
    (net (code "203") (name "VCC_12p0_CARD") (class "Default")
      (node (ref "J0") (pin "100") (pinfunction "12V_100") (pintype "power_in"))
      (node (ref "J0") (pin "106") (pinfunction "12V_106") (pintype "power_in"))
      (node (ref "J0") (pin "112") (pinfunction "12V_112") (pintype "power_in"))
      (node (ref "J0") (pin "118") (pinfunction "12V_118") (pintype "power_in"))
      (node (ref "J0") (pin "124") (pinfunction "12V_124") (pintype "power_in"))
      (node (ref "J0") (pin "130") (pinfunction "12V_130") (pintype "power_in"))
      (node (ref "J0") (pin "136") (pinfunction "12V_136") (pintype "power_in"))
      (node (ref "J0") (pin "142") (pinfunction "12V_142") (pintype "power_in"))
      (node (ref "J0") (pin "148") (pinfunction "12V_148") (pintype "power_in"))
      (node (ref "J0") (pin "154") (pinfunction "12V_154") (pintype "power_in"))
      (node (ref "J0") (pin "46") (pinfunction "12V_46") (pintype "power_in"))
      (node (ref "J0") (pin "52") (pinfunction "12V_52") (pintype "power_in"))
      (node (ref "J0") (pin "58") (pinfunction "12V_58") (pintype "power_in"))
      (node (ref "J0") (pin "64") (pinfunction "12V_64") (pintype "power_in"))
      (node (ref "J0") (pin "70") (pinfunction "12V_70") (pintype "power_in"))
      (node (ref "J0") (pin "76") (pinfunction "12V_76") (pintype "power_in"))
      (node (ref "J0") (pin "82") (pinfunction "12V_82") (pintype "power_in"))
      (node (ref "J0") (pin "88") (pinfunction "12V_88") (pintype "power_in"))
      (node (ref "J0") (pin "94") (pinfunction "12V_94") (pintype "power_in"))
      (node (ref "J1") (pin "100") (pinfunction "12V_100") (pintype "power_in"))
      (node (ref "J1") (pin "106") (pinfunction "12V_106") (pintype "power_in"))
      (node (ref "J1") (pin "112") (pinfunction "12V_112") (pintype "power_in"))
      (node (ref "J1") (pin "118") (pinfunction "12V_118") (pintype "power_in"))
      (node (ref "J1") (pin "124") (pinfunction "12V_124") (pintype "power_in"))
      (node (ref "J1") (pin "130") (pinfunction "12V_130") (pintype "power_in"))
      (node (ref "J1") (pin "136") (pinfunction "12V_136") (pintype "power_in"))
      (node (ref "J1") (pin "142") (pinfunction "12V_142") (pintype "power_in"))
      (node (ref "J1") (pin "148") (pinfunction "12V_148") (pintype "power_in"))
      (node (ref "J1") (pin "154") (pinfunction "12V_154") (pintype "power_in"))
      (node (ref "J1") (pin "46") (pinfunction "12V_46") (pintype "power_in"))
      (node (ref "J1") (pin "52") (pinfunction "12V_52") (pintype "power_in"))
      (node (ref "J1") (pin "58") (pinfunction "12V_58") (pintype "power_in"))
      (node (ref "J1") (pin "64") (pinfunction "12V_64") (pintype "power_in"))
      (node (ref "J1") (pin "70") (pinfunction "12V_70") (pintype "power_in"))
      (node (ref "J1") (pin "76") (pinfunction "12V_76") (pintype "power_in"))
      (node (ref "J1") (pin "82") (pinfunction "12V_82") (pintype "power_in"))
      (node (ref "J1") (pin "88") (pinfunction "12V_88") (pintype "power_in"))
      (node (ref "J1") (pin "94") (pinfunction "12V_94") (pintype "power_in"))
      (node (ref "J2") (pin "100") (pinfunction "12V_100") (pintype "power_in"))
      (node (ref "J2") (pin "106") (pinfunction "12V_106") (pintype "power_in"))
      (node (ref "J2") (pin "112") (pinfunction "12V_112") (pintype "power_in"))
      (node (ref "J2") (pin "118") (pinfunction "12V_118") (pintype "power_in"))
      (node (ref "J2") (pin "124") (pinfunction "12V_124") (pintype "power_in"))
      (node (ref "J2") (pin "130") (pinfunction "12V_130") (pintype "power_in"))
      (node (ref "J2") (pin "136") (pinfunction "12V_136") (pintype "power_in"))
      (node (ref "J2") (pin "142") (pinfunction "12V_142") (pintype "power_in"))
      (node (ref "J2") (pin "148") (pinfunction "12V_148") (pintype "power_in"))
      (node (ref "J2") (pin "154") (pinfunction "12V_154") (pintype "power_in"))
      (node (ref "J2") (pin "46") (pinfunction "12V_46") (pintype "power_in"))
      (node (ref "J2") (pin "52") (pinfunction "12V_52") (pintype "power_in"))
      (node (ref "J2") (pin "58") (pinfunction "12V_58") (pintype "power_in"))
      (node (ref "J2") (pin "64") (pinfunction "12V_64") (pintype "power_in"))
      (node (ref "J2") (pin "70") (pinfunction "12V_70") (pintype "power_in"))
      (node (ref "J2") (pin "76") (pinfunction "12V_76") (pintype "power_in"))
      (node (ref "J2") (pin "82") (pinfunction "12V_82") (pintype "power_in"))
      (node (ref "J2") (pin "88") (pinfunction "12V_88") (pintype "power_in"))
      (node (ref "J2") (pin "94") (pinfunction "12V_94") (pintype "power_in"))
      (node (ref "J3") (pin "100") (pinfunction "12V_100") (pintype "power_in"))
      (node (ref "J3") (pin "106") (pinfunction "12V_106") (pintype "power_in"))
      (node (ref "J3") (pin "112") (pinfunction "12V_112") (pintype "power_in"))
      (node (ref "J3") (pin "118") (pinfunction "12V_118") (pintype "power_in"))
      (node (ref "J3") (pin "124") (pinfunction "12V_124") (pintype "power_in"))
      (node (ref "J3") (pin "130") (pinfunction "12V_130") (pintype "power_in"))
      (node (ref "J3") (pin "136") (pinfunction "12V_136") (pintype "power_in"))
      (node (ref "J3") (pin "142") (pinfunction "12V_142") (pintype "power_in"))
      (node (ref "J3") (pin "148") (pinfunction "12V_148") (pintype "power_in"))
      (node (ref "J3") (pin "154") (pinfunction "12V_154") (pintype "power_in"))
      (node (ref "J3") (pin "46") (pinfunction "12V_46") (pintype "power_in"))
      (node (ref "J3") (pin "52") (pinfunction "12V_52") (pintype "power_in"))
      (node (ref "J3") (pin "58") (pinfunction "12V_58") (pintype "power_in"))
      (node (ref "J3") (pin "64") (pinfunction "12V_64") (pintype "power_in"))
      (node (ref "J3") (pin "70") (pinfunction "12V_70") (pintype "power_in"))
      (node (ref "J3") (pin "76") (pinfunction "12V_76") (pintype "power_in"))
      (node (ref "J3") (pin "82") (pinfunction "12V_82") (pintype "power_in"))
      (node (ref "J3") (pin "88") (pinfunction "12V_88") (pintype "power_in"))
      (node (ref "J3") (pin "94") (pinfunction "12V_94") (pintype "power_in"))
    )
    (net (code "204") (name "VCC_VADJ_CARD") (class "Default")
      (node (ref "J0") (pin "131") (pinfunction "131_131") (pintype "passive"))
      (node (ref "J0") (pin "133") (pinfunction "133_133") (pintype "passive"))
      (node (ref "J1") (pin "131") (pinfunction "131_131") (pintype "passive"))
      (node (ref "J1") (pin "133") (pinfunction "133_133") (pintype "passive"))
      (node (ref "J2") (pin "131") (pinfunction "131_131") (pintype "passive"))
      (node (ref "J2") (pin "133") (pinfunction "133_133") (pintype "passive"))
      (node (ref "J3") (pin "131") (pinfunction "131_131") (pintype "passive"))
      (node (ref "J3") (pin "133") (pinfunction "133_133") (pintype "passive"))
    )
    (net (code "205") (name "unconnected-(J0-PSNTn-Pad160)") (class "Default")
      (node (ref "J0") (pin "160") (pinfunction "PSNTn_160") (pintype "power_in+no_connect"))
    )
    (net (code "206") (name "unconnected-(J0-Pad1)") (class "Default")
      (node (ref "J0") (pin "1") (pinfunction "1_1") (pintype "passive+no_connect"))
    )
    (net (code "207") (name "unconnected-(J0-Pad2)") (class "Default")
      (node (ref "J0") (pin "2") (pinfunction "2_2") (pintype "passive+no_connect"))
    )
    (net (code "208") (name "unconnected-(J0-Pad3)") (class "Default")
      (node (ref "J0") (pin "3") (pinfunction "3_3") (pintype "passive+no_connect"))
    )
    (net (code "209") (name "unconnected-(J0-Pad4)") (class "Default")
      (node (ref "J0") (pin "4") (pinfunction "4_4") (pintype "passive+no_connect"))
    )
    (net (code "210") (name "unconnected-(J0-Pad5)") (class "Default")
      (node (ref "J0") (pin "5") (pinfunction "5_5") (pintype "passive+no_connect"))
    )
    (net (code "211") (name "unconnected-(J0-Pad6)") (class "Default")
      (node (ref "J0") (pin "6") (pinfunction "6_6") (pintype "passive+no_connect"))
    )
    (net (code "212") (name "unconnected-(J0-Pad7)") (class "Default")
      (node (ref "J0") (pin "7") (pinfunction "7_7") (pintype "passive+no_connect"))
    )
    (net (code "213") (name "unconnected-(J0-Pad8)") (class "Default")
      (node (ref "J0") (pin "8") (pinfunction "8_8") (pintype "passive+no_connect"))
    )
    (net (code "214") (name "unconnected-(J0-Pad9)") (class "Default")
      (node (ref "J0") (pin "9") (pinfunction "9_9") (pintype "passive+no_connect"))
    )
    (net (code "215") (name "unconnected-(J0-Pad10)") (class "Default")
      (node (ref "J0") (pin "10") (pinfunction "10_10") (pintype "passive+no_connect"))
    )
    (net (code "216") (name "unconnected-(J0-Pad11)") (class "Default")
      (node (ref "J0") (pin "11") (pinfunction "11_11") (pintype "passive+no_connect"))
    )
    (net (code "217") (name "unconnected-(J0-Pad12)") (class "Default")
      (node (ref "J0") (pin "12") (pinfunction "12_12") (pintype "passive"))
    )
    (net (code "218") (name "unconnected-(J0-Pad13)") (class "Default")
      (node (ref "J0") (pin "13") (pinfunction "13_13") (pintype "passive+no_connect"))
    )
    (net (code "219") (name "unconnected-(J0-Pad14)") (class "Default")
      (node (ref "J0") (pin "14") (pinfunction "14_14") (pintype "passive+no_connect"))
    )
    (net (code "220") (name "unconnected-(J0-Pad15)") (class "Default")
      (node (ref "J0") (pin "15") (pinfunction "15_15") (pintype "passive+no_connect"))
    )
    (net (code "221") (name "unconnected-(J0-Pad16)") (class "Default")
      (node (ref "J0") (pin "16") (pinfunction "16_16") (pintype "passive+no_connect"))
    )
    (net (code "222") (name "unconnected-(J0-Pad17)") (class "Default")
      (node (ref "J0") (pin "17") (pinfunction "17_17") (pintype "passive+no_connect"))
    )
    (net (code "223") (name "unconnected-(J0-Pad18)") (class "Default")
      (node (ref "J0") (pin "18") (pinfunction "18_18") (pintype "passive+no_connect"))
    )
    (net (code "224") (name "unconnected-(J0-Pad19)") (class "Default")
      (node (ref "J0") (pin "19") (pinfunction "19_19") (pintype "passive+no_connect"))
    )
    (net (code "225") (name "unconnected-(J0-Pad20)") (class "Default")
      (node (ref "J0") (pin "20") (pinfunction "20_20") (pintype "passive+no_connect"))
    )
    (net (code "226") (name "unconnected-(J0-Pad21)") (class "Default")
      (node (ref "J0") (pin "21") (pinfunction "21_21") (pintype "passive+no_connect"))
    )
    (net (code "227") (name "unconnected-(J0-Pad22)") (class "Default")
      (node (ref "J0") (pin "22") (pinfunction "22_22") (pintype "passive+no_connect"))
    )
    (net (code "228") (name "unconnected-(J0-Pad23)") (class "Default")
      (node (ref "J0") (pin "23") (pinfunction "23_23") (pintype "passive+no_connect"))
    )
    (net (code "229") (name "unconnected-(J0-Pad24)") (class "Default")
      (node (ref "J0") (pin "24") (pinfunction "24_24") (pintype "passive+no_connect"))
    )
    (net (code "230") (name "unconnected-(J0-Pad25)") (class "Default")
      (node (ref "J0") (pin "25") (pinfunction "25_25") (pintype "passive+no_connect"))
    )
    (net (code "231") (name "unconnected-(J0-Pad27)") (class "Default")
      (node (ref "J0") (pin "27") (pinfunction "27_27") (pintype "passive+no_connect"))
    )
    (net (code "232") (name "unconnected-(J0-Pad29)") (class "Default")
      (node (ref "J0") (pin "29") (pinfunction "29_29") (pintype "passive+no_connect"))
    )
    (net (code "233") (name "unconnected-(J0-Pad31)") (class "Default")
      (node (ref "J0") (pin "31") (pinfunction "31_31") (pintype "passive+no_connect"))
    )
    (net (code "234") (name "unconnected-(J0-Pad98)") (class "Default")
      (node (ref "J0") (pin "98") (pinfunction "98_98") (pintype "passive+no_connect"))
    )
    (net (code "235") (name "unconnected-(J0-Pad101)") (class "Default")
      (node (ref "J0") (pin "101") (pinfunction "101_101") (pintype "passive"))
    )
    (net (code "236") (name "unconnected-(J0-Pad102)") (class "Default")
      (node (ref "J0") (pin "102") (pinfunction "102_102") (pintype "passive"))
    )
    (net (code "237") (name "unconnected-(J0-Pad103)") (class "Default")
      (node (ref "J0") (pin "103") (pinfunction "103_103") (pintype "passive"))
    )
    (net (code "238") (name "unconnected-(J0-Pad104)") (class "Default")
      (node (ref "J0") (pin "104") (pinfunction "104_104") (pintype "passive"))
    )
    (net (code "239") (name "unconnected-(J0-Pad107)") (class "Default")
      (node (ref "J0") (pin "107") (pinfunction "107_107") (pintype "passive"))
    )
    (net (code "240") (name "unconnected-(J0-Pad108)") (class "Default")
      (node (ref "J0") (pin "108") (pinfunction "108_108") (pintype "passive"))
    )
    (net (code "241") (name "unconnected-(J0-Pad109)") (class "Default")
      (node (ref "J0") (pin "109") (pinfunction "109_109") (pintype "passive"))
    )
    (net (code "242") (name "unconnected-(J0-Pad110)") (class "Default")
      (node (ref "J0") (pin "110") (pinfunction "110_110") (pintype "passive"))
    )
    (net (code "243") (name "unconnected-(J0-Pad113)") (class "Default")
      (node (ref "J0") (pin "113") (pinfunction "113_113") (pintype "passive"))
    )
    (net (code "244") (name "unconnected-(J0-Pad114)") (class "Default")
      (node (ref "J0") (pin "114") (pinfunction "114_114") (pintype "passive"))
    )
    (net (code "245") (name "unconnected-(J0-Pad116)") (class "Default")
      (node (ref "J0") (pin "116") (pinfunction "116_116") (pintype "passive"))
    )
    (net (code "246") (name "unconnected-(J0-Pad125)") (class "Default")
      (node (ref "J0") (pin "125") (pinfunction "125_125") (pintype "passive+no_connect"))
    )
    (net (code "247") (name "unconnected-(J0-Pad126)") (class "Default")
      (node (ref "J0") (pin "126") (pinfunction "126_126") (pintype "passive+no_connect"))
    )
    (net (code "248") (name "unconnected-(J0-Pad127)") (class "Default")
      (node (ref "J0") (pin "127") (pinfunction "127_127") (pintype "passive+no_connect"))
    )
    (net (code "249") (name "unconnected-(J0-Pad128)") (class "Default")
      (node (ref "J0") (pin "128") (pinfunction "128_128") (pintype "passive+no_connect"))
    )
    (net (code "250") (name "unconnected-(J0-Pad132)") (class "Default")
      (node (ref "J0") (pin "132") (pinfunction "132_132") (pintype "passive"))
    )
    (net (code "251") (name "unconnected-(J0-Pad134)") (class "Default")
      (node (ref "J0") (pin "134") (pinfunction "134_134") (pintype "passive"))
    )
    (net (code "252") (name "unconnected-(J0-Pad137)") (class "Default")
      (node (ref "J0") (pin "137") (pinfunction "137_137") (pintype "passive+no_connect"))
    )
    (net (code "253") (name "unconnected-(J0-Pad138)") (class "Default")
      (node (ref "J0") (pin "138") (pinfunction "138_138") (pintype "passive+no_connect"))
    )
    (net (code "254") (name "unconnected-(J0-Pad139)") (class "Default")
      (node (ref "J0") (pin "139") (pinfunction "139_139") (pintype "passive+no_connect"))
    )
    (net (code "255") (name "unconnected-(J0-Pad140)") (class "Default")
      (node (ref "J0") (pin "140") (pinfunction "140_140") (pintype "passive+no_connect"))
    )
    (net (code "256") (name "unconnected-(J0-Pad143)") (class "Default")
      (node (ref "J0") (pin "143") (pinfunction "143_143") (pintype "passive+no_connect"))
    )
    (net (code "257") (name "unconnected-(J0-Pad144)") (class "Default")
      (node (ref "J0") (pin "144") (pinfunction "144_144") (pintype "passive+no_connect"))
    )
    (net (code "258") (name "unconnected-(J0-Pad145)") (class "Default")
      (node (ref "J0") (pin "145") (pinfunction "145_145") (pintype "passive+no_connect"))
    )
    (net (code "259") (name "unconnected-(J0-Pad146)") (class "Default")
      (node (ref "J0") (pin "146") (pinfunction "146_146") (pintype "passive+no_connect"))
    )
    (net (code "260") (name "unconnected-(J0-Pad149)") (class "Default")
      (node (ref "J0") (pin "149") (pinfunction "149_149") (pintype "passive"))
    )
    (net (code "261") (name "unconnected-(J0-Pad150)") (class "Default")
      (node (ref "J0") (pin "150") (pinfunction "150_150") (pintype "passive+no_connect"))
    )
    (net (code "262") (name "unconnected-(J0-Pad151)") (class "Default")
      (node (ref "J0") (pin "151") (pinfunction "151_151") (pintype "passive"))
    )
    (net (code "263") (name "unconnected-(J0-Pad152)") (class "Default")
      (node (ref "J0") (pin "152") (pinfunction "152_152") (pintype "passive+no_connect"))
    )
    (net (code "264") (name "unconnected-(J0-Pad155)") (class "Default")
      (node (ref "J0") (pin "155") (pinfunction "155_155") (pintype "passive+no_connect"))
    )
    (net (code "265") (name "unconnected-(J0-Pad156)") (class "Default")
      (node (ref "J0") (pin "156") (pinfunction "156_156") (pintype "passive+no_connect"))
    )
    (net (code "266") (name "unconnected-(J0-Pad157)") (class "Default")
      (node (ref "J0") (pin "157") (pinfunction "157_157") (pintype "passive+no_connect"))
    )
    (net (code "267") (name "unconnected-(J0-Pad158)") (class "Default")
      (node (ref "J0") (pin "158") (pinfunction "158_158") (pintype "passive+no_connect"))
    )
    (net (code "268") (name "unconnected-(J0-SCL-Pad34)") (class "Default")
      (node (ref "J0") (pin "34") (pinfunction "SCL_34") (pintype "passive+no_connect"))
    )
    (net (code "269") (name "unconnected-(J0-SDA-Pad33)") (class "Default")
      (node (ref "J0") (pin "33") (pinfunction "SDA_33") (pintype "passive+no_connect"))
    )
    (net (code "270") (name "unconnected-(J0-TCK-Pad35)") (class "Default")
      (node (ref "J0") (pin "35") (pinfunction "TCK_35") (pintype "passive+no_connect"))
    )
    (net (code "271") (name "unconnected-(J0-TDI-Pad38)") (class "Default")
      (node (ref "J0") (pin "38") (pinfunction "TDI_38") (pintype "passive+no_connect"))
    )
    (net (code "272") (name "unconnected-(J0-TDO-Pad37)") (class "Default")
      (node (ref "J0") (pin "37") (pinfunction "TDO_37") (pintype "passive+no_connect"))
    )
    (net (code "273") (name "unconnected-(J0-TMS-Pad36)") (class "Default")
      (node (ref "J0") (pin "36") (pinfunction "TMS_36") (pintype "passive+no_connect"))
    )
    (net (code "274") (name "unconnected-(J1-PSNTn-Pad160)") (class "Default")
      (node (ref "J1") (pin "160") (pinfunction "PSNTn_160") (pintype "power_in+no_connect"))
    )
    (net (code "275") (name "unconnected-(J1-Pad1)") (class "Default")
      (node (ref "J1") (pin "1") (pinfunction "1_1") (pintype "passive+no_connect"))
    )
    (net (code "276") (name "unconnected-(J1-Pad2)") (class "Default")
      (node (ref "J1") (pin "2") (pinfunction "2_2") (pintype "passive+no_connect"))
    )
    (net (code "277") (name "unconnected-(J1-Pad3)") (class "Default")
      (node (ref "J1") (pin "3") (pinfunction "3_3") (pintype "passive+no_connect"))
    )
    (net (code "278") (name "unconnected-(J1-Pad4)") (class "Default")
      (node (ref "J1") (pin "4") (pinfunction "4_4") (pintype "passive+no_connect"))
    )
    (net (code "279") (name "unconnected-(J1-Pad5)") (class "Default")
      (node (ref "J1") (pin "5") (pinfunction "5_5") (pintype "passive+no_connect"))
    )
    (net (code "280") (name "unconnected-(J1-Pad6)") (class "Default")
      (node (ref "J1") (pin "6") (pinfunction "6_6") (pintype "passive+no_connect"))
    )
    (net (code "281") (name "unconnected-(J1-Pad7)") (class "Default")
      (node (ref "J1") (pin "7") (pinfunction "7_7") (pintype "passive+no_connect"))
    )
    (net (code "282") (name "unconnected-(J1-Pad8)") (class "Default")
      (node (ref "J1") (pin "8") (pinfunction "8_8") (pintype "passive+no_connect"))
    )
    (net (code "283") (name "unconnected-(J1-Pad9)") (class "Default")
      (node (ref "J1") (pin "9") (pinfunction "9_9") (pintype "passive+no_connect"))
    )
    (net (code "284") (name "unconnected-(J1-Pad10)") (class "Default")
      (node (ref "J1") (pin "10") (pinfunction "10_10") (pintype "passive+no_connect"))
    )
    (net (code "285") (name "unconnected-(J1-Pad11)") (class "Default")
      (node (ref "J1") (pin "11") (pinfunction "11_11") (pintype "passive+no_connect"))
    )
    (net (code "286") (name "unconnected-(J1-Pad12)") (class "Default")
      (node (ref "J1") (pin "12") (pinfunction "12_12") (pintype "passive"))
    )
    (net (code "287") (name "unconnected-(J1-Pad13)") (class "Default")
      (node (ref "J1") (pin "13") (pinfunction "13_13") (pintype "passive+no_connect"))
    )
    (net (code "288") (name "unconnected-(J1-Pad14)") (class "Default")
      (node (ref "J1") (pin "14") (pinfunction "14_14") (pintype "passive+no_connect"))
    )
    (net (code "289") (name "unconnected-(J1-Pad15)") (class "Default")
      (node (ref "J1") (pin "15") (pinfunction "15_15") (pintype "passive+no_connect"))
    )
    (net (code "290") (name "unconnected-(J1-Pad16)") (class "Default")
      (node (ref "J1") (pin "16") (pinfunction "16_16") (pintype "passive+no_connect"))
    )
    (net (code "291") (name "unconnected-(J1-Pad17)") (class "Default")
      (node (ref "J1") (pin "17") (pinfunction "17_17") (pintype "passive+no_connect"))
    )
    (net (code "292") (name "unconnected-(J1-Pad18)") (class "Default")
      (node (ref "J1") (pin "18") (pinfunction "18_18") (pintype "passive+no_connect"))
    )
    (net (code "293") (name "unconnected-(J1-Pad19)") (class "Default")
      (node (ref "J1") (pin "19") (pinfunction "19_19") (pintype "passive+no_connect"))
    )
    (net (code "294") (name "unconnected-(J1-Pad20)") (class "Default")
      (node (ref "J1") (pin "20") (pinfunction "20_20") (pintype "passive+no_connect"))
    )
    (net (code "295") (name "unconnected-(J1-Pad21)") (class "Default")
      (node (ref "J1") (pin "21") (pinfunction "21_21") (pintype "passive+no_connect"))
    )
    (net (code "296") (name "unconnected-(J1-Pad22)") (class "Default")
      (node (ref "J1") (pin "22") (pinfunction "22_22") (pintype "passive+no_connect"))
    )
    (net (code "297") (name "unconnected-(J1-Pad23)") (class "Default")
      (node (ref "J1") (pin "23") (pinfunction "23_23") (pintype "passive+no_connect"))
    )
    (net (code "298") (name "unconnected-(J1-Pad24)") (class "Default")
      (node (ref "J1") (pin "24") (pinfunction "24_24") (pintype "passive+no_connect"))
    )
    (net (code "299") (name "unconnected-(J1-Pad25)") (class "Default")
      (node (ref "J1") (pin "25") (pinfunction "25_25") (pintype "passive+no_connect"))
    )
    (net (code "300") (name "unconnected-(J1-Pad27)") (class "Default")
      (node (ref "J1") (pin "27") (pinfunction "27_27") (pintype "passive+no_connect"))
    )
    (net (code "301") (name "unconnected-(J1-Pad29)") (class "Default")
      (node (ref "J1") (pin "29") (pinfunction "29_29") (pintype "passive+no_connect"))
    )
    (net (code "302") (name "unconnected-(J1-Pad31)") (class "Default")
      (node (ref "J1") (pin "31") (pinfunction "31_31") (pintype "passive+no_connect"))
    )
    (net (code "303") (name "unconnected-(J1-Pad98)") (class "Default")
      (node (ref "J1") (pin "98") (pinfunction "98_98") (pintype "passive+no_connect"))
    )
    (net (code "304") (name "unconnected-(J1-Pad101)") (class "Default")
      (node (ref "J1") (pin "101") (pinfunction "101_101") (pintype "passive"))
    )
    (net (code "305") (name "unconnected-(J1-Pad102)") (class "Default")
      (node (ref "J1") (pin "102") (pinfunction "102_102") (pintype "passive"))
    )
    (net (code "306") (name "unconnected-(J1-Pad103)") (class "Default")
      (node (ref "J1") (pin "103") (pinfunction "103_103") (pintype "passive"))
    )
    (net (code "307") (name "unconnected-(J1-Pad104)") (class "Default")
      (node (ref "J1") (pin "104") (pinfunction "104_104") (pintype "passive"))
    )
    (net (code "308") (name "unconnected-(J1-Pad107)") (class "Default")
      (node (ref "J1") (pin "107") (pinfunction "107_107") (pintype "passive"))
    )
    (net (code "309") (name "unconnected-(J1-Pad108)") (class "Default")
      (node (ref "J1") (pin "108") (pinfunction "108_108") (pintype "passive"))
    )
    (net (code "310") (name "unconnected-(J1-Pad109)") (class "Default")
      (node (ref "J1") (pin "109") (pinfunction "109_109") (pintype "passive"))
    )
    (net (code "311") (name "unconnected-(J1-Pad110)") (class "Default")
      (node (ref "J1") (pin "110") (pinfunction "110_110") (pintype "passive"))
    )
    (net (code "312") (name "unconnected-(J1-Pad113)") (class "Default")
      (node (ref "J1") (pin "113") (pinfunction "113_113") (pintype "passive"))
    )
    (net (code "313") (name "unconnected-(J1-Pad114)") (class "Default")
      (node (ref "J1") (pin "114") (pinfunction "114_114") (pintype "passive"))
    )
    (net (code "314") (name "unconnected-(J1-Pad116)") (class "Default")
      (node (ref "J1") (pin "116") (pinfunction "116_116") (pintype "passive"))
    )
    (net (code "315") (name "unconnected-(J1-Pad125)") (class "Default")
      (node (ref "J1") (pin "125") (pinfunction "125_125") (pintype "passive+no_connect"))
    )
    (net (code "316") (name "unconnected-(J1-Pad126)") (class "Default")
      (node (ref "J1") (pin "126") (pinfunction "126_126") (pintype "passive+no_connect"))
    )
    (net (code "317") (name "unconnected-(J1-Pad127)") (class "Default")
      (node (ref "J1") (pin "127") (pinfunction "127_127") (pintype "passive+no_connect"))
    )
    (net (code "318") (name "unconnected-(J1-Pad128)") (class "Default")
      (node (ref "J1") (pin "128") (pinfunction "128_128") (pintype "passive+no_connect"))
    )
    (net (code "319") (name "unconnected-(J1-Pad132)") (class "Default")
      (node (ref "J1") (pin "132") (pinfunction "132_132") (pintype "passive"))
    )
    (net (code "320") (name "unconnected-(J1-Pad134)") (class "Default")
      (node (ref "J1") (pin "134") (pinfunction "134_134") (pintype "passive"))
    )
    (net (code "321") (name "unconnected-(J1-Pad137)") (class "Default")
      (node (ref "J1") (pin "137") (pinfunction "137_137") (pintype "passive+no_connect"))
    )
    (net (code "322") (name "unconnected-(J1-Pad138)") (class "Default")
      (node (ref "J1") (pin "138") (pinfunction "138_138") (pintype "passive+no_connect"))
    )
    (net (code "323") (name "unconnected-(J1-Pad139)") (class "Default")
      (node (ref "J1") (pin "139") (pinfunction "139_139") (pintype "passive+no_connect"))
    )
    (net (code "324") (name "unconnected-(J1-Pad140)") (class "Default")
      (node (ref "J1") (pin "140") (pinfunction "140_140") (pintype "passive+no_connect"))
    )
    (net (code "325") (name "unconnected-(J1-Pad143)") (class "Default")
      (node (ref "J1") (pin "143") (pinfunction "143_143") (pintype "passive+no_connect"))
    )
    (net (code "326") (name "unconnected-(J1-Pad144)") (class "Default")
      (node (ref "J1") (pin "144") (pinfunction "144_144") (pintype "passive+no_connect"))
    )
    (net (code "327") (name "unconnected-(J1-Pad145)") (class "Default")
      (node (ref "J1") (pin "145") (pinfunction "145_145") (pintype "passive+no_connect"))
    )
    (net (code "328") (name "unconnected-(J1-Pad146)") (class "Default")
      (node (ref "J1") (pin "146") (pinfunction "146_146") (pintype "passive+no_connect"))
    )
    (net (code "329") (name "unconnected-(J1-Pad149)") (class "Default")
      (node (ref "J1") (pin "149") (pinfunction "149_149") (pintype "passive"))
    )
    (net (code "330") (name "unconnected-(J1-Pad150)") (class "Default")
      (node (ref "J1") (pin "150") (pinfunction "150_150") (pintype "passive+no_connect"))
    )
    (net (code "331") (name "unconnected-(J1-Pad151)") (class "Default")
      (node (ref "J1") (pin "151") (pinfunction "151_151") (pintype "passive"))
    )
    (net (code "332") (name "unconnected-(J1-Pad152)") (class "Default")
      (node (ref "J1") (pin "152") (pinfunction "152_152") (pintype "passive+no_connect"))
    )
    (net (code "333") (name "unconnected-(J1-Pad155)") (class "Default")
      (node (ref "J1") (pin "155") (pinfunction "155_155") (pintype "passive+no_connect"))
    )
    (net (code "334") (name "unconnected-(J1-Pad156)") (class "Default")
      (node (ref "J1") (pin "156") (pinfunction "156_156") (pintype "passive+no_connect"))
    )
    (net (code "335") (name "unconnected-(J1-Pad157)") (class "Default")
      (node (ref "J1") (pin "157") (pinfunction "157_157") (pintype "passive+no_connect"))
    )
    (net (code "336") (name "unconnected-(J1-Pad158)") (class "Default")
      (node (ref "J1") (pin "158") (pinfunction "158_158") (pintype "passive+no_connect"))
    )
    (net (code "337") (name "unconnected-(J1-SCL-Pad34)") (class "Default")
      (node (ref "J1") (pin "34") (pinfunction "SCL_34") (pintype "passive+no_connect"))
    )
    (net (code "338") (name "unconnected-(J1-SDA-Pad33)") (class "Default")
      (node (ref "J1") (pin "33") (pinfunction "SDA_33") (pintype "passive+no_connect"))
    )
    (net (code "339") (name "unconnected-(J1-TCK-Pad35)") (class "Default")
      (node (ref "J1") (pin "35") (pinfunction "TCK_35") (pintype "passive+no_connect"))
    )
    (net (code "340") (name "unconnected-(J1-TDI-Pad38)") (class "Default")
      (node (ref "J1") (pin "38") (pinfunction "TDI_38") (pintype "passive+no_connect"))
    )
    (net (code "341") (name "unconnected-(J1-TDO-Pad37)") (class "Default")
      (node (ref "J1") (pin "37") (pinfunction "TDO_37") (pintype "passive+no_connect"))
    )
    (net (code "342") (name "unconnected-(J1-TMS-Pad36)") (class "Default")
      (node (ref "J1") (pin "36") (pinfunction "TMS_36") (pintype "passive+no_connect"))
    )
    (net (code "343") (name "unconnected-(J2-PSNTn-Pad160)") (class "Default")
      (node (ref "J2") (pin "160") (pinfunction "PSNTn_160") (pintype "power_in+no_connect"))
    )
    (net (code "344") (name "unconnected-(J2-Pad1)") (class "Default")
      (node (ref "J2") (pin "1") (pinfunction "1_1") (pintype "passive+no_connect"))
    )
    (net (code "345") (name "unconnected-(J2-Pad2)") (class "Default")
      (node (ref "J2") (pin "2") (pinfunction "2_2") (pintype "passive+no_connect"))
    )
    (net (code "346") (name "unconnected-(J2-Pad3)") (class "Default")
      (node (ref "J2") (pin "3") (pinfunction "3_3") (pintype "passive+no_connect"))
    )
    (net (code "347") (name "unconnected-(J2-Pad4)") (class "Default")
      (node (ref "J2") (pin "4") (pinfunction "4_4") (pintype "passive+no_connect"))
    )
    (net (code "348") (name "unconnected-(J2-Pad5)") (class "Default")
      (node (ref "J2") (pin "5") (pinfunction "5_5") (pintype "passive+no_connect"))
    )
    (net (code "349") (name "unconnected-(J2-Pad6)") (class "Default")
      (node (ref "J2") (pin "6") (pinfunction "6_6") (pintype "passive+no_connect"))
    )
    (net (code "350") (name "unconnected-(J2-Pad7)") (class "Default")
      (node (ref "J2") (pin "7") (pinfunction "7_7") (pintype "passive+no_connect"))
    )
    (net (code "351") (name "unconnected-(J2-Pad8)") (class "Default")
      (node (ref "J2") (pin "8") (pinfunction "8_8") (pintype "passive+no_connect"))
    )
    (net (code "352") (name "unconnected-(J2-Pad9)") (class "Default")
      (node (ref "J2") (pin "9") (pinfunction "9_9") (pintype "passive+no_connect"))
    )
    (net (code "353") (name "unconnected-(J2-Pad10)") (class "Default")
      (node (ref "J2") (pin "10") (pinfunction "10_10") (pintype "passive+no_connect"))
    )
    (net (code "354") (name "unconnected-(J2-Pad11)") (class "Default")
      (node (ref "J2") (pin "11") (pinfunction "11_11") (pintype "passive+no_connect"))
    )
    (net (code "355") (name "unconnected-(J2-Pad12)") (class "Default")
      (node (ref "J2") (pin "12") (pinfunction "12_12") (pintype "passive"))
    )
    (net (code "356") (name "unconnected-(J2-Pad13)") (class "Default")
      (node (ref "J2") (pin "13") (pinfunction "13_13") (pintype "passive+no_connect"))
    )
    (net (code "357") (name "unconnected-(J2-Pad14)") (class "Default")
      (node (ref "J2") (pin "14") (pinfunction "14_14") (pintype "passive+no_connect"))
    )
    (net (code "358") (name "unconnected-(J2-Pad15)") (class "Default")
      (node (ref "J2") (pin "15") (pinfunction "15_15") (pintype "passive+no_connect"))
    )
    (net (code "359") (name "unconnected-(J2-Pad16)") (class "Default")
      (node (ref "J2") (pin "16") (pinfunction "16_16") (pintype "passive+no_connect"))
    )
    (net (code "360") (name "unconnected-(J2-Pad17)") (class "Default")
      (node (ref "J2") (pin "17") (pinfunction "17_17") (pintype "passive+no_connect"))
    )
    (net (code "361") (name "unconnected-(J2-Pad18)") (class "Default")
      (node (ref "J2") (pin "18") (pinfunction "18_18") (pintype "passive+no_connect"))
    )
    (net (code "362") (name "unconnected-(J2-Pad19)") (class "Default")
      (node (ref "J2") (pin "19") (pinfunction "19_19") (pintype "passive+no_connect"))
    )
    (net (code "363") (name "unconnected-(J2-Pad20)") (class "Default")
      (node (ref "J2") (pin "20") (pinfunction "20_20") (pintype "passive+no_connect"))
    )
    (net (code "364") (name "unconnected-(J2-Pad21)") (class "Default")
      (node (ref "J2") (pin "21") (pinfunction "21_21") (pintype "passive+no_connect"))
    )
    (net (code "365") (name "unconnected-(J2-Pad22)") (class "Default")
      (node (ref "J2") (pin "22") (pinfunction "22_22") (pintype "passive+no_connect"))
    )
    (net (code "366") (name "unconnected-(J2-Pad23)") (class "Default")
      (node (ref "J2") (pin "23") (pinfunction "23_23") (pintype "passive+no_connect"))
    )
    (net (code "367") (name "unconnected-(J2-Pad24)") (class "Default")
      (node (ref "J2") (pin "24") (pinfunction "24_24") (pintype "passive+no_connect"))
    )
    (net (code "368") (name "unconnected-(J2-Pad25)") (class "Default")
      (node (ref "J2") (pin "25") (pinfunction "25_25") (pintype "passive+no_connect"))
    )
    (net (code "369") (name "unconnected-(J2-Pad27)") (class "Default")
      (node (ref "J2") (pin "27") (pinfunction "27_27") (pintype "passive+no_connect"))
    )
    (net (code "370") (name "unconnected-(J2-Pad29)") (class "Default")
      (node (ref "J2") (pin "29") (pinfunction "29_29") (pintype "passive+no_connect"))
    )
    (net (code "371") (name "unconnected-(J2-Pad31)") (class "Default")
      (node (ref "J2") (pin "31") (pinfunction "31_31") (pintype "passive+no_connect"))
    )
    (net (code "372") (name "unconnected-(J2-Pad98)") (class "Default")
      (node (ref "J2") (pin "98") (pinfunction "98_98") (pintype "passive+no_connect"))
    )
    (net (code "373") (name "unconnected-(J2-Pad101)") (class "Default")
      (node (ref "J2") (pin "101") (pinfunction "101_101") (pintype "passive"))
    )
    (net (code "374") (name "unconnected-(J2-Pad102)") (class "Default")
      (node (ref "J2") (pin "102") (pinfunction "102_102") (pintype "passive"))
    )
    (net (code "375") (name "unconnected-(J2-Pad103)") (class "Default")
      (node (ref "J2") (pin "103") (pinfunction "103_103") (pintype "passive"))
    )
    (net (code "376") (name "unconnected-(J2-Pad104)") (class "Default")
      (node (ref "J2") (pin "104") (pinfunction "104_104") (pintype "passive"))
    )
    (net (code "377") (name "unconnected-(J2-Pad107)") (class "Default")
      (node (ref "J2") (pin "107") (pinfunction "107_107") (pintype "passive"))
    )
    (net (code "378") (name "unconnected-(J2-Pad108)") (class "Default")
      (node (ref "J2") (pin "108") (pinfunction "108_108") (pintype "passive"))
    )
    (net (code "379") (name "unconnected-(J2-Pad109)") (class "Default")
      (node (ref "J2") (pin "109") (pinfunction "109_109") (pintype "passive"))
    )
    (net (code "380") (name "unconnected-(J2-Pad110)") (class "Default")
      (node (ref "J2") (pin "110") (pinfunction "110_110") (pintype "passive"))
    )
    (net (code "381") (name "unconnected-(J2-Pad113)") (class "Default")
      (node (ref "J2") (pin "113") (pinfunction "113_113") (pintype "passive"))
    )
    (net (code "382") (name "unconnected-(J2-Pad114)") (class "Default")
      (node (ref "J2") (pin "114") (pinfunction "114_114") (pintype "passive"))
    )
    (net (code "383") (name "unconnected-(J2-Pad116)") (class "Default")
      (node (ref "J2") (pin "116") (pinfunction "116_116") (pintype "passive"))
    )
    (net (code "384") (name "unconnected-(J2-Pad125)") (class "Default")
      (node (ref "J2") (pin "125") (pinfunction "125_125") (pintype "passive+no_connect"))
    )
    (net (code "385") (name "unconnected-(J2-Pad126)") (class "Default")
      (node (ref "J2") (pin "126") (pinfunction "126_126") (pintype "passive+no_connect"))
    )
    (net (code "386") (name "unconnected-(J2-Pad127)") (class "Default")
      (node (ref "J2") (pin "127") (pinfunction "127_127") (pintype "passive+no_connect"))
    )
    (net (code "387") (name "unconnected-(J2-Pad128)") (class "Default")
      (node (ref "J2") (pin "128") (pinfunction "128_128") (pintype "passive+no_connect"))
    )
    (net (code "388") (name "unconnected-(J2-Pad132)") (class "Default")
      (node (ref "J2") (pin "132") (pinfunction "132_132") (pintype "passive"))
    )
    (net (code "389") (name "unconnected-(J2-Pad134)") (class "Default")
      (node (ref "J2") (pin "134") (pinfunction "134_134") (pintype "passive"))
    )
    (net (code "390") (name "unconnected-(J2-Pad137)") (class "Default")
      (node (ref "J2") (pin "137") (pinfunction "137_137") (pintype "passive+no_connect"))
    )
    (net (code "391") (name "unconnected-(J2-Pad138)") (class "Default")
      (node (ref "J2") (pin "138") (pinfunction "138_138") (pintype "passive+no_connect"))
    )
    (net (code "392") (name "unconnected-(J2-Pad139)") (class "Default")
      (node (ref "J2") (pin "139") (pinfunction "139_139") (pintype "passive+no_connect"))
    )
    (net (code "393") (name "unconnected-(J2-Pad140)") (class "Default")
      (node (ref "J2") (pin "140") (pinfunction "140_140") (pintype "passive+no_connect"))
    )
    (net (code "394") (name "unconnected-(J2-Pad143)") (class "Default")
      (node (ref "J2") (pin "143") (pinfunction "143_143") (pintype "passive+no_connect"))
    )
    (net (code "395") (name "unconnected-(J2-Pad144)") (class "Default")
      (node (ref "J2") (pin "144") (pinfunction "144_144") (pintype "passive+no_connect"))
    )
    (net (code "396") (name "unconnected-(J2-Pad145)") (class "Default")
      (node (ref "J2") (pin "145") (pinfunction "145_145") (pintype "passive+no_connect"))
    )
    (net (code "397") (name "unconnected-(J2-Pad146)") (class "Default")
      (node (ref "J2") (pin "146") (pinfunction "146_146") (pintype "passive+no_connect"))
    )
    (net (code "398") (name "unconnected-(J2-Pad149)") (class "Default")
      (node (ref "J2") (pin "149") (pinfunction "149_149") (pintype "passive"))
    )
    (net (code "399") (name "unconnected-(J2-Pad150)") (class "Default")
      (node (ref "J2") (pin "150") (pinfunction "150_150") (pintype "passive+no_connect"))
    )
    (net (code "400") (name "unconnected-(J2-Pad151)") (class "Default")
      (node (ref "J2") (pin "151") (pinfunction "151_151") (pintype "passive"))
    )
    (net (code "401") (name "unconnected-(J2-Pad152)") (class "Default")
      (node (ref "J2") (pin "152") (pinfunction "152_152") (pintype "passive+no_connect"))
    )
    (net (code "402") (name "unconnected-(J2-Pad155)") (class "Default")
      (node (ref "J2") (pin "155") (pinfunction "155_155") (pintype "passive+no_connect"))
    )
    (net (code "403") (name "unconnected-(J2-Pad156)") (class "Default")
      (node (ref "J2") (pin "156") (pinfunction "156_156") (pintype "passive+no_connect"))
    )
    (net (code "404") (name "unconnected-(J2-Pad157)") (class "Default")
      (node (ref "J2") (pin "157") (pinfunction "157_157") (pintype "passive+no_connect"))
    )
    (net (code "405") (name "unconnected-(J2-Pad158)") (class "Default")
      (node (ref "J2") (pin "158") (pinfunction "158_158") (pintype "passive+no_connect"))
    )
    (net (code "406") (name "unconnected-(J2-SCL-Pad34)") (class "Default")
      (node (ref "J2") (pin "34") (pinfunction "SCL_34") (pintype "passive+no_connect"))
    )
    (net (code "407") (name "unconnected-(J2-SDA-Pad33)") (class "Default")
      (node (ref "J2") (pin "33") (pinfunction "SDA_33") (pintype "passive+no_connect"))
    )
    (net (code "408") (name "unconnected-(J2-TCK-Pad35)") (class "Default")
      (node (ref "J2") (pin "35") (pinfunction "TCK_35") (pintype "passive+no_connect"))
    )
    (net (code "409") (name "unconnected-(J2-TDI-Pad38)") (class "Default")
      (node (ref "J2") (pin "38") (pinfunction "TDI_38") (pintype "passive+no_connect"))
    )
    (net (code "410") (name "unconnected-(J2-TDO-Pad37)") (class "Default")
      (node (ref "J2") (pin "37") (pinfunction "TDO_37") (pintype "passive+no_connect"))
    )
    (net (code "411") (name "unconnected-(J2-TMS-Pad36)") (class "Default")
      (node (ref "J2") (pin "36") (pinfunction "TMS_36") (pintype "passive+no_connect"))
    )
    (net (code "412") (name "unconnected-(J3-PSNTn-Pad160)") (class "Default")
      (node (ref "J3") (pin "160") (pinfunction "PSNTn_160") (pintype "power_in+no_connect"))
    )
    (net (code "413") (name "unconnected-(J3-Pad1)") (class "Default")
      (node (ref "J3") (pin "1") (pinfunction "1_1") (pintype "passive+no_connect"))
    )
    (net (code "414") (name "unconnected-(J3-Pad2)") (class "Default")
      (node (ref "J3") (pin "2") (pinfunction "2_2") (pintype "passive+no_connect"))
    )
    (net (code "415") (name "unconnected-(J3-Pad3)") (class "Default")
      (node (ref "J3") (pin "3") (pinfunction "3_3") (pintype "passive+no_connect"))
    )
    (net (code "416") (name "unconnected-(J3-Pad4)") (class "Default")
      (node (ref "J3") (pin "4") (pinfunction "4_4") (pintype "passive+no_connect"))
    )
    (net (code "417") (name "unconnected-(J3-Pad5)") (class "Default")
      (node (ref "J3") (pin "5") (pinfunction "5_5") (pintype "passive+no_connect"))
    )
    (net (code "418") (name "unconnected-(J3-Pad6)") (class "Default")
      (node (ref "J3") (pin "6") (pinfunction "6_6") (pintype "passive+no_connect"))
    )
    (net (code "419") (name "unconnected-(J3-Pad7)") (class "Default")
      (node (ref "J3") (pin "7") (pinfunction "7_7") (pintype "passive+no_connect"))
    )
    (net (code "420") (name "unconnected-(J3-Pad8)") (class "Default")
      (node (ref "J3") (pin "8") (pinfunction "8_8") (pintype "passive+no_connect"))
    )
    (net (code "421") (name "unconnected-(J3-Pad9)") (class "Default")
      (node (ref "J3") (pin "9") (pinfunction "9_9") (pintype "passive+no_connect"))
    )
    (net (code "422") (name "unconnected-(J3-Pad10)") (class "Default")
      (node (ref "J3") (pin "10") (pinfunction "10_10") (pintype "passive+no_connect"))
    )
    (net (code "423") (name "unconnected-(J3-Pad11)") (class "Default")
      (node (ref "J3") (pin "11") (pinfunction "11_11") (pintype "passive+no_connect"))
    )
    (net (code "424") (name "unconnected-(J3-Pad12)") (class "Default")
      (node (ref "J3") (pin "12") (pinfunction "12_12") (pintype "passive"))
    )
    (net (code "425") (name "unconnected-(J3-Pad13)") (class "Default")
      (node (ref "J3") (pin "13") (pinfunction "13_13") (pintype "passive+no_connect"))
    )
    (net (code "426") (name "unconnected-(J3-Pad14)") (class "Default")
      (node (ref "J3") (pin "14") (pinfunction "14_14") (pintype "passive+no_connect"))
    )
    (net (code "427") (name "unconnected-(J3-Pad15)") (class "Default")
      (node (ref "J3") (pin "15") (pinfunction "15_15") (pintype "passive+no_connect"))
    )
    (net (code "428") (name "unconnected-(J3-Pad16)") (class "Default")
      (node (ref "J3") (pin "16") (pinfunction "16_16") (pintype "passive+no_connect"))
    )
    (net (code "429") (name "unconnected-(J3-Pad17)") (class "Default")
      (node (ref "J3") (pin "17") (pinfunction "17_17") (pintype "passive+no_connect"))
    )
    (net (code "430") (name "unconnected-(J3-Pad18)") (class "Default")
      (node (ref "J3") (pin "18") (pinfunction "18_18") (pintype "passive+no_connect"))
    )
    (net (code "431") (name "unconnected-(J3-Pad19)") (class "Default")
      (node (ref "J3") (pin "19") (pinfunction "19_19") (pintype "passive+no_connect"))
    )
    (net (code "432") (name "unconnected-(J3-Pad20)") (class "Default")
      (node (ref "J3") (pin "20") (pinfunction "20_20") (pintype "passive+no_connect"))
    )
    (net (code "433") (name "unconnected-(J3-Pad21)") (class "Default")
      (node (ref "J3") (pin "21") (pinfunction "21_21") (pintype "passive+no_connect"))
    )
    (net (code "434") (name "unconnected-(J3-Pad22)") (class "Default")
      (node (ref "J3") (pin "22") (pinfunction "22_22") (pintype "passive+no_connect"))
    )
    (net (code "435") (name "unconnected-(J3-Pad23)") (class "Default")
      (node (ref "J3") (pin "23") (pinfunction "23_23") (pintype "passive+no_connect"))
    )
    (net (code "436") (name "unconnected-(J3-Pad24)") (class "Default")
      (node (ref "J3") (pin "24") (pinfunction "24_24") (pintype "passive+no_connect"))
    )
    (net (code "437") (name "unconnected-(J3-Pad25)") (class "Default")
      (node (ref "J3") (pin "25") (pinfunction "25_25") (pintype "passive+no_connect"))
    )
    (net (code "438") (name "unconnected-(J3-Pad27)") (class "Default")
      (node (ref "J3") (pin "27") (pinfunction "27_27") (pintype "passive+no_connect"))
    )
    (net (code "439") (name "unconnected-(J3-Pad29)") (class "Default")
      (node (ref "J3") (pin "29") (pinfunction "29_29") (pintype "passive+no_connect"))
    )
    (net (code "440") (name "unconnected-(J3-Pad31)") (class "Default")
      (node (ref "J3") (pin "31") (pinfunction "31_31") (pintype "passive+no_connect"))
    )
    (net (code "441") (name "unconnected-(J3-Pad98)") (class "Default")
      (node (ref "J3") (pin "98") (pinfunction "98_98") (pintype "passive+no_connect"))
    )
    (net (code "442") (name "unconnected-(J3-Pad101)") (class "Default")
      (node (ref "J3") (pin "101") (pinfunction "101_101") (pintype "passive"))
    )
    (net (code "443") (name "unconnected-(J3-Pad102)") (class "Default")
      (node (ref "J3") (pin "102") (pinfunction "102_102") (pintype "passive"))
    )
    (net (code "444") (name "unconnected-(J3-Pad103)") (class "Default")
      (node (ref "J3") (pin "103") (pinfunction "103_103") (pintype "passive"))
    )
    (net (code "445") (name "unconnected-(J3-Pad104)") (class "Default")
      (node (ref "J3") (pin "104") (pinfunction "104_104") (pintype "passive"))
    )
    (net (code "446") (name "unconnected-(J3-Pad107)") (class "Default")
      (node (ref "J3") (pin "107") (pinfunction "107_107") (pintype "passive"))
    )
    (net (code "447") (name "unconnected-(J3-Pad108)") (class "Default")
      (node (ref "J3") (pin "108") (pinfunction "108_108") (pintype "passive"))
    )
    (net (code "448") (name "unconnected-(J3-Pad109)") (class "Default")
      (node (ref "J3") (pin "109") (pinfunction "109_109") (pintype "passive"))
    )
    (net (code "449") (name "unconnected-(J3-Pad110)") (class "Default")
      (node (ref "J3") (pin "110") (pinfunction "110_110") (pintype "passive"))
    )
    (net (code "450") (name "unconnected-(J3-Pad113)") (class "Default")
      (node (ref "J3") (pin "113") (pinfunction "113_113") (pintype "passive"))
    )
    (net (code "451") (name "unconnected-(J3-Pad114)") (class "Default")
      (node (ref "J3") (pin "114") (pinfunction "114_114") (pintype "passive"))
    )
    (net (code "452") (name "unconnected-(J3-Pad116)") (class "Default")
      (node (ref "J3") (pin "116") (pinfunction "116_116") (pintype "passive"))
    )
    (net (code "453") (name "unconnected-(J3-Pad125)") (class "Default")
      (node (ref "J3") (pin "125") (pinfunction "125_125") (pintype "passive+no_connect"))
    )
    (net (code "454") (name "unconnected-(J3-Pad126)") (class "Default")
      (node (ref "J3") (pin "126") (pinfunction "126_126") (pintype "passive+no_connect"))
    )
    (net (code "455") (name "unconnected-(J3-Pad127)") (class "Default")
      (node (ref "J3") (pin "127") (pinfunction "127_127") (pintype "passive+no_connect"))
    )
    (net (code "456") (name "unconnected-(J3-Pad128)") (class "Default")
      (node (ref "J3") (pin "128") (pinfunction "128_128") (pintype "passive+no_connect"))
    )
    (net (code "457") (name "unconnected-(J3-Pad132)") (class "Default")
      (node (ref "J3") (pin "132") (pinfunction "132_132") (pintype "passive"))
    )
    (net (code "458") (name "unconnected-(J3-Pad134)") (class "Default")
      (node (ref "J3") (pin "134") (pinfunction "134_134") (pintype "passive"))
    )
    (net (code "459") (name "unconnected-(J3-Pad137)") (class "Default")
      (node (ref "J3") (pin "137") (pinfunction "137_137") (pintype "passive+no_connect"))
    )
    (net (code "460") (name "unconnected-(J3-Pad138)") (class "Default")
      (node (ref "J3") (pin "138") (pinfunction "138_138") (pintype "passive+no_connect"))
    )
    (net (code "461") (name "unconnected-(J3-Pad139)") (class "Default")
      (node (ref "J3") (pin "139") (pinfunction "139_139") (pintype "passive+no_connect"))
    )
    (net (code "462") (name "unconnected-(J3-Pad140)") (class "Default")
      (node (ref "J3") (pin "140") (pinfunction "140_140") (pintype "passive+no_connect"))
    )
    (net (code "463") (name "unconnected-(J3-Pad143)") (class "Default")
      (node (ref "J3") (pin "143") (pinfunction "143_143") (pintype "passive+no_connect"))
    )
    (net (code "464") (name "unconnected-(J3-Pad144)") (class "Default")
      (node (ref "J3") (pin "144") (pinfunction "144_144") (pintype "passive+no_connect"))
    )
    (net (code "465") (name "unconnected-(J3-Pad145)") (class "Default")
      (node (ref "J3") (pin "145") (pinfunction "145_145") (pintype "passive+no_connect"))
    )
    (net (code "466") (name "unconnected-(J3-Pad146)") (class "Default")
      (node (ref "J3") (pin "146") (pinfunction "146_146") (pintype "passive+no_connect"))
    )
    (net (code "467") (name "unconnected-(J3-Pad149)") (class "Default")
      (node (ref "J3") (pin "149") (pinfunction "149_149") (pintype "passive"))
    )
    (net (code "468") (name "unconnected-(J3-Pad150)") (class "Default")
      (node (ref "J3") (pin "150") (pinfunction "150_150") (pintype "passive+no_connect"))
    )
    (net (code "469") (name "unconnected-(J3-Pad151)") (class "Default")
      (node (ref "J3") (pin "151") (pinfunction "151_151") (pintype "passive"))
    )
    (net (code "470") (name "unconnected-(J3-Pad152)") (class "Default")
      (node (ref "J3") (pin "152") (pinfunction "152_152") (pintype "passive+no_connect"))
    )
    (net (code "471") (name "unconnected-(J3-Pad155)") (class "Default")
      (node (ref "J3") (pin "155") (pinfunction "155_155") (pintype "passive+no_connect"))
    )
    (net (code "472") (name "unconnected-(J3-Pad156)") (class "Default")
      (node (ref "J3") (pin "156") (pinfunction "156_156") (pintype "passive+no_connect"))
    )
    (net (code "473") (name "unconnected-(J3-Pad157)") (class "Default")
      (node (ref "J3") (pin "157") (pinfunction "157_157") (pintype "passive+no_connect"))
    )
    (net (code "474") (name "unconnected-(J3-Pad158)") (class "Default")
      (node (ref "J3") (pin "158") (pinfunction "158_158") (pintype "passive+no_connect"))
    )
    (net (code "475") (name "unconnected-(J3-SCL-Pad34)") (class "Default")
      (node (ref "J3") (pin "34") (pinfunction "SCL_34") (pintype "passive+no_connect"))
    )
    (net (code "476") (name "unconnected-(J3-SDA-Pad33)") (class "Default")
      (node (ref "J3") (pin "33") (pinfunction "SDA_33") (pintype "passive+no_connect"))
    )
    (net (code "477") (name "unconnected-(J3-TCK-Pad35)") (class "Default")
      (node (ref "J3") (pin "35") (pinfunction "TCK_35") (pintype "passive+no_connect"))
    )
    (net (code "478") (name "unconnected-(J3-TDI-Pad38)") (class "Default")
      (node (ref "J3") (pin "38") (pinfunction "TDI_38") (pintype "passive+no_connect"))
    )
    (net (code "479") (name "unconnected-(J3-TDO-Pad37)") (class "Default")
      (node (ref "J3") (pin "37") (pinfunction "TDO_37") (pintype "passive+no_connect"))
    )
    (net (code "480") (name "unconnected-(J3-TMS-Pad36)") (class "Default")
      (node (ref "J3") (pin "36") (pinfunction "TMS_36") (pintype "passive+no_connect"))
    )
  )
)
